# 8bit_RAM.net
KiCad netlist of a schematic drawn in Altium Designer
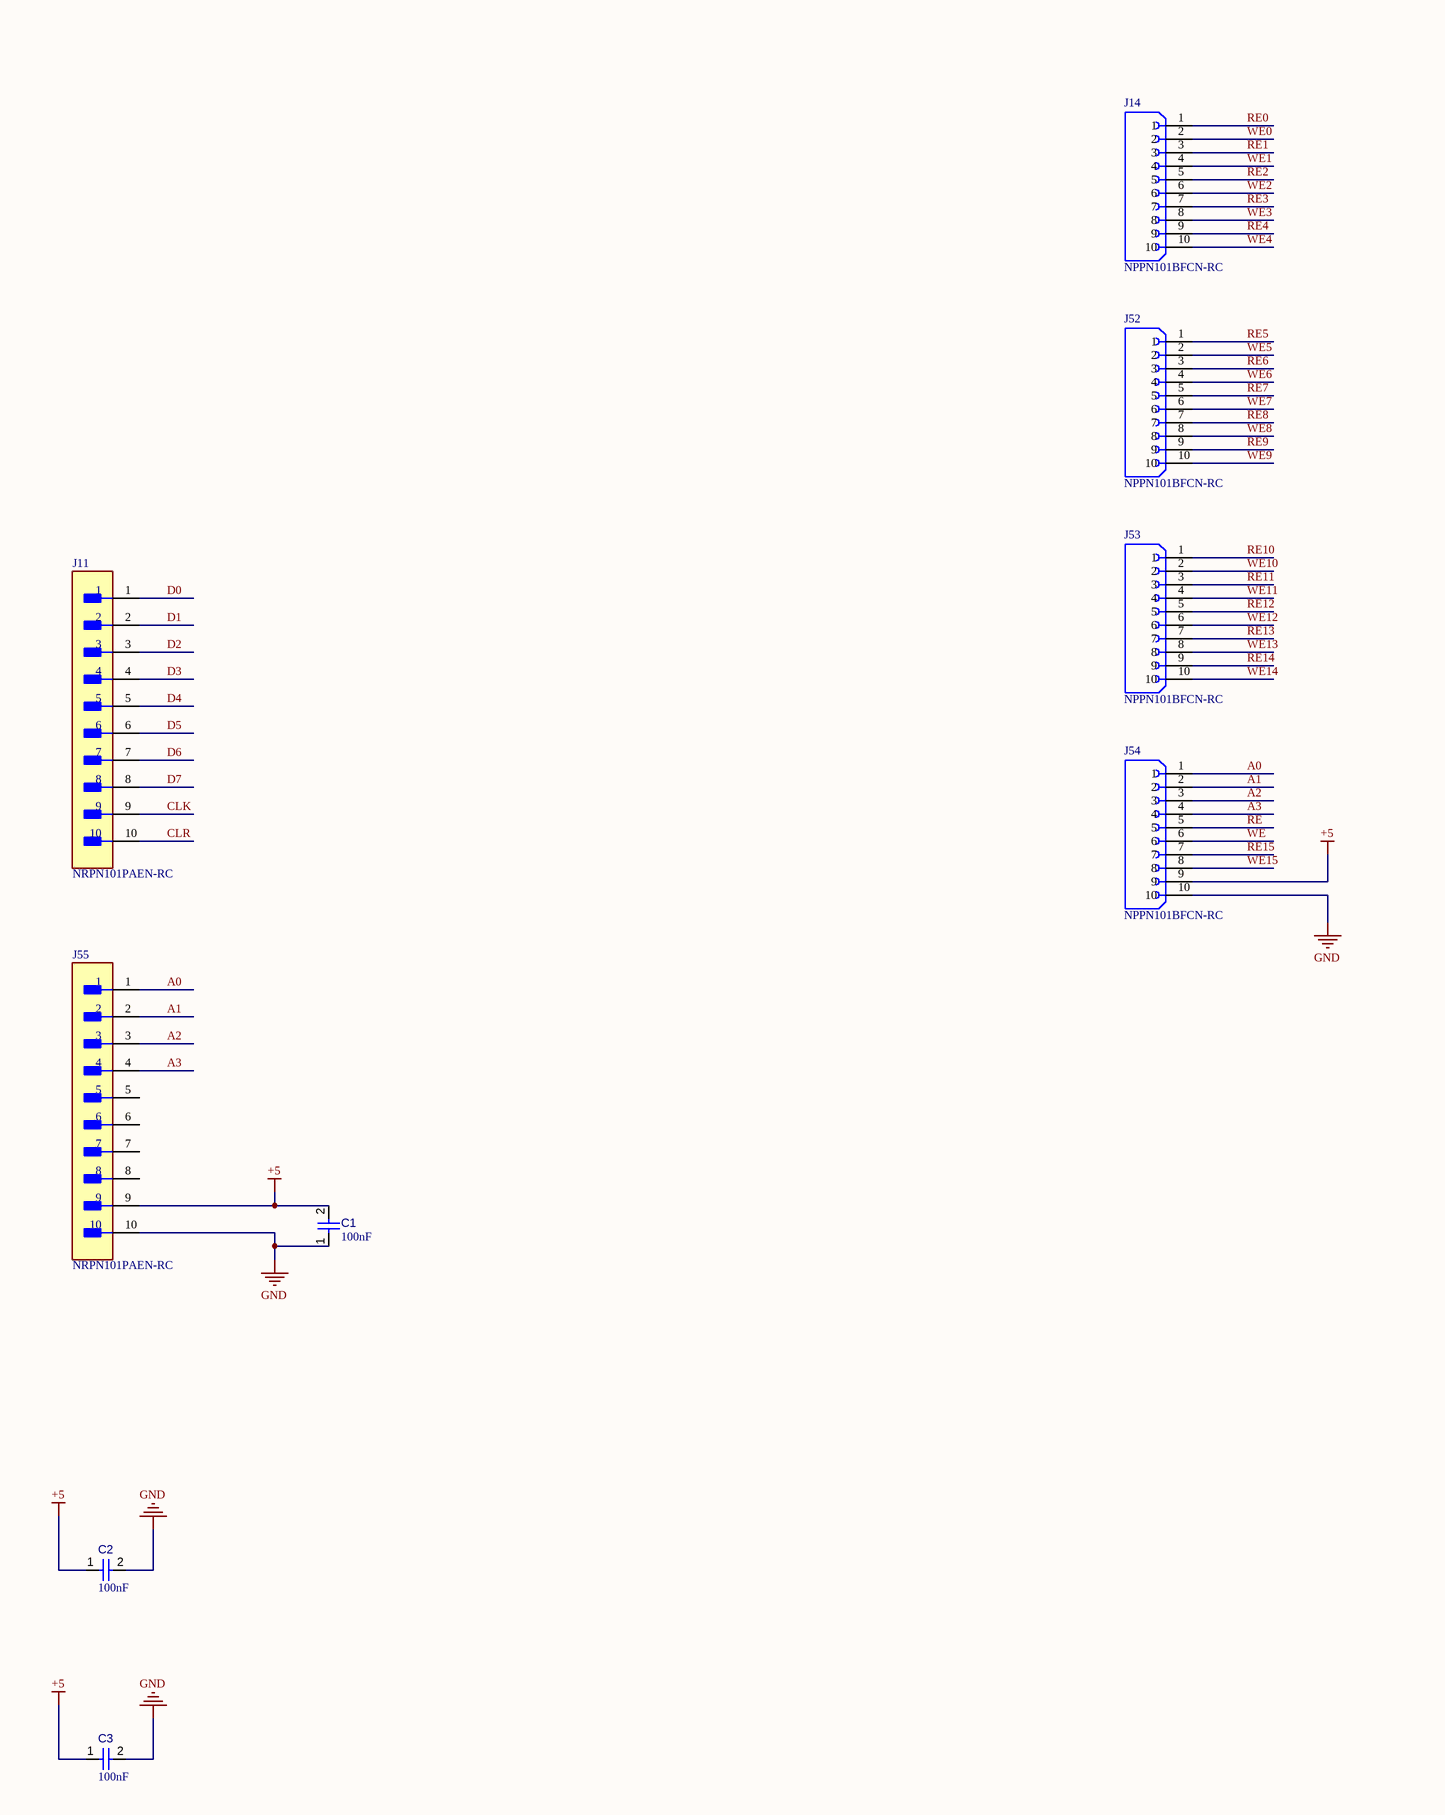
[diagram p0: 8bit_RAM.SchDoc, top left]
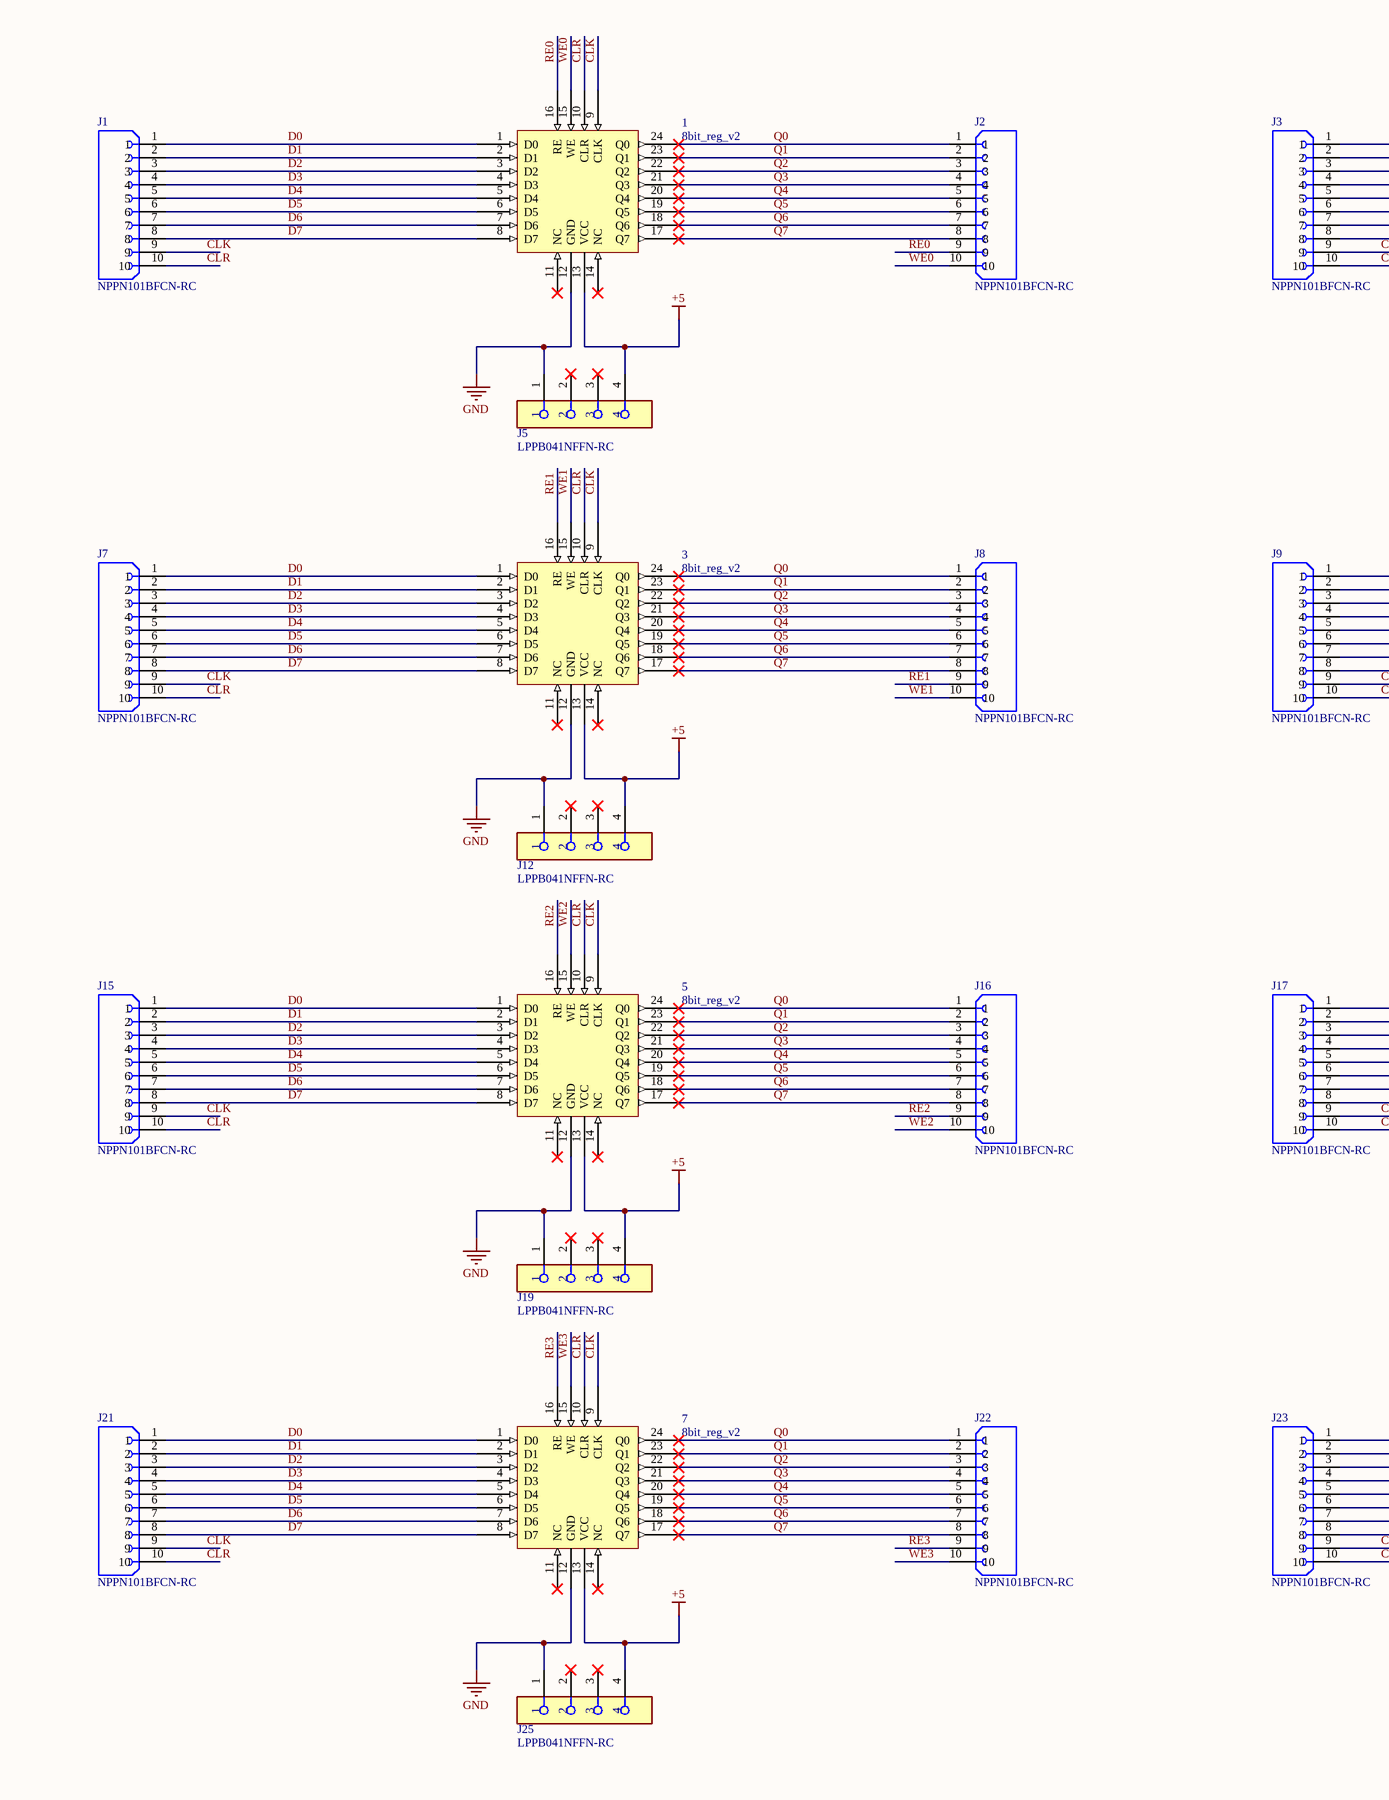
[diagram p1: 8bit_RAM.SchDoc, top middle]
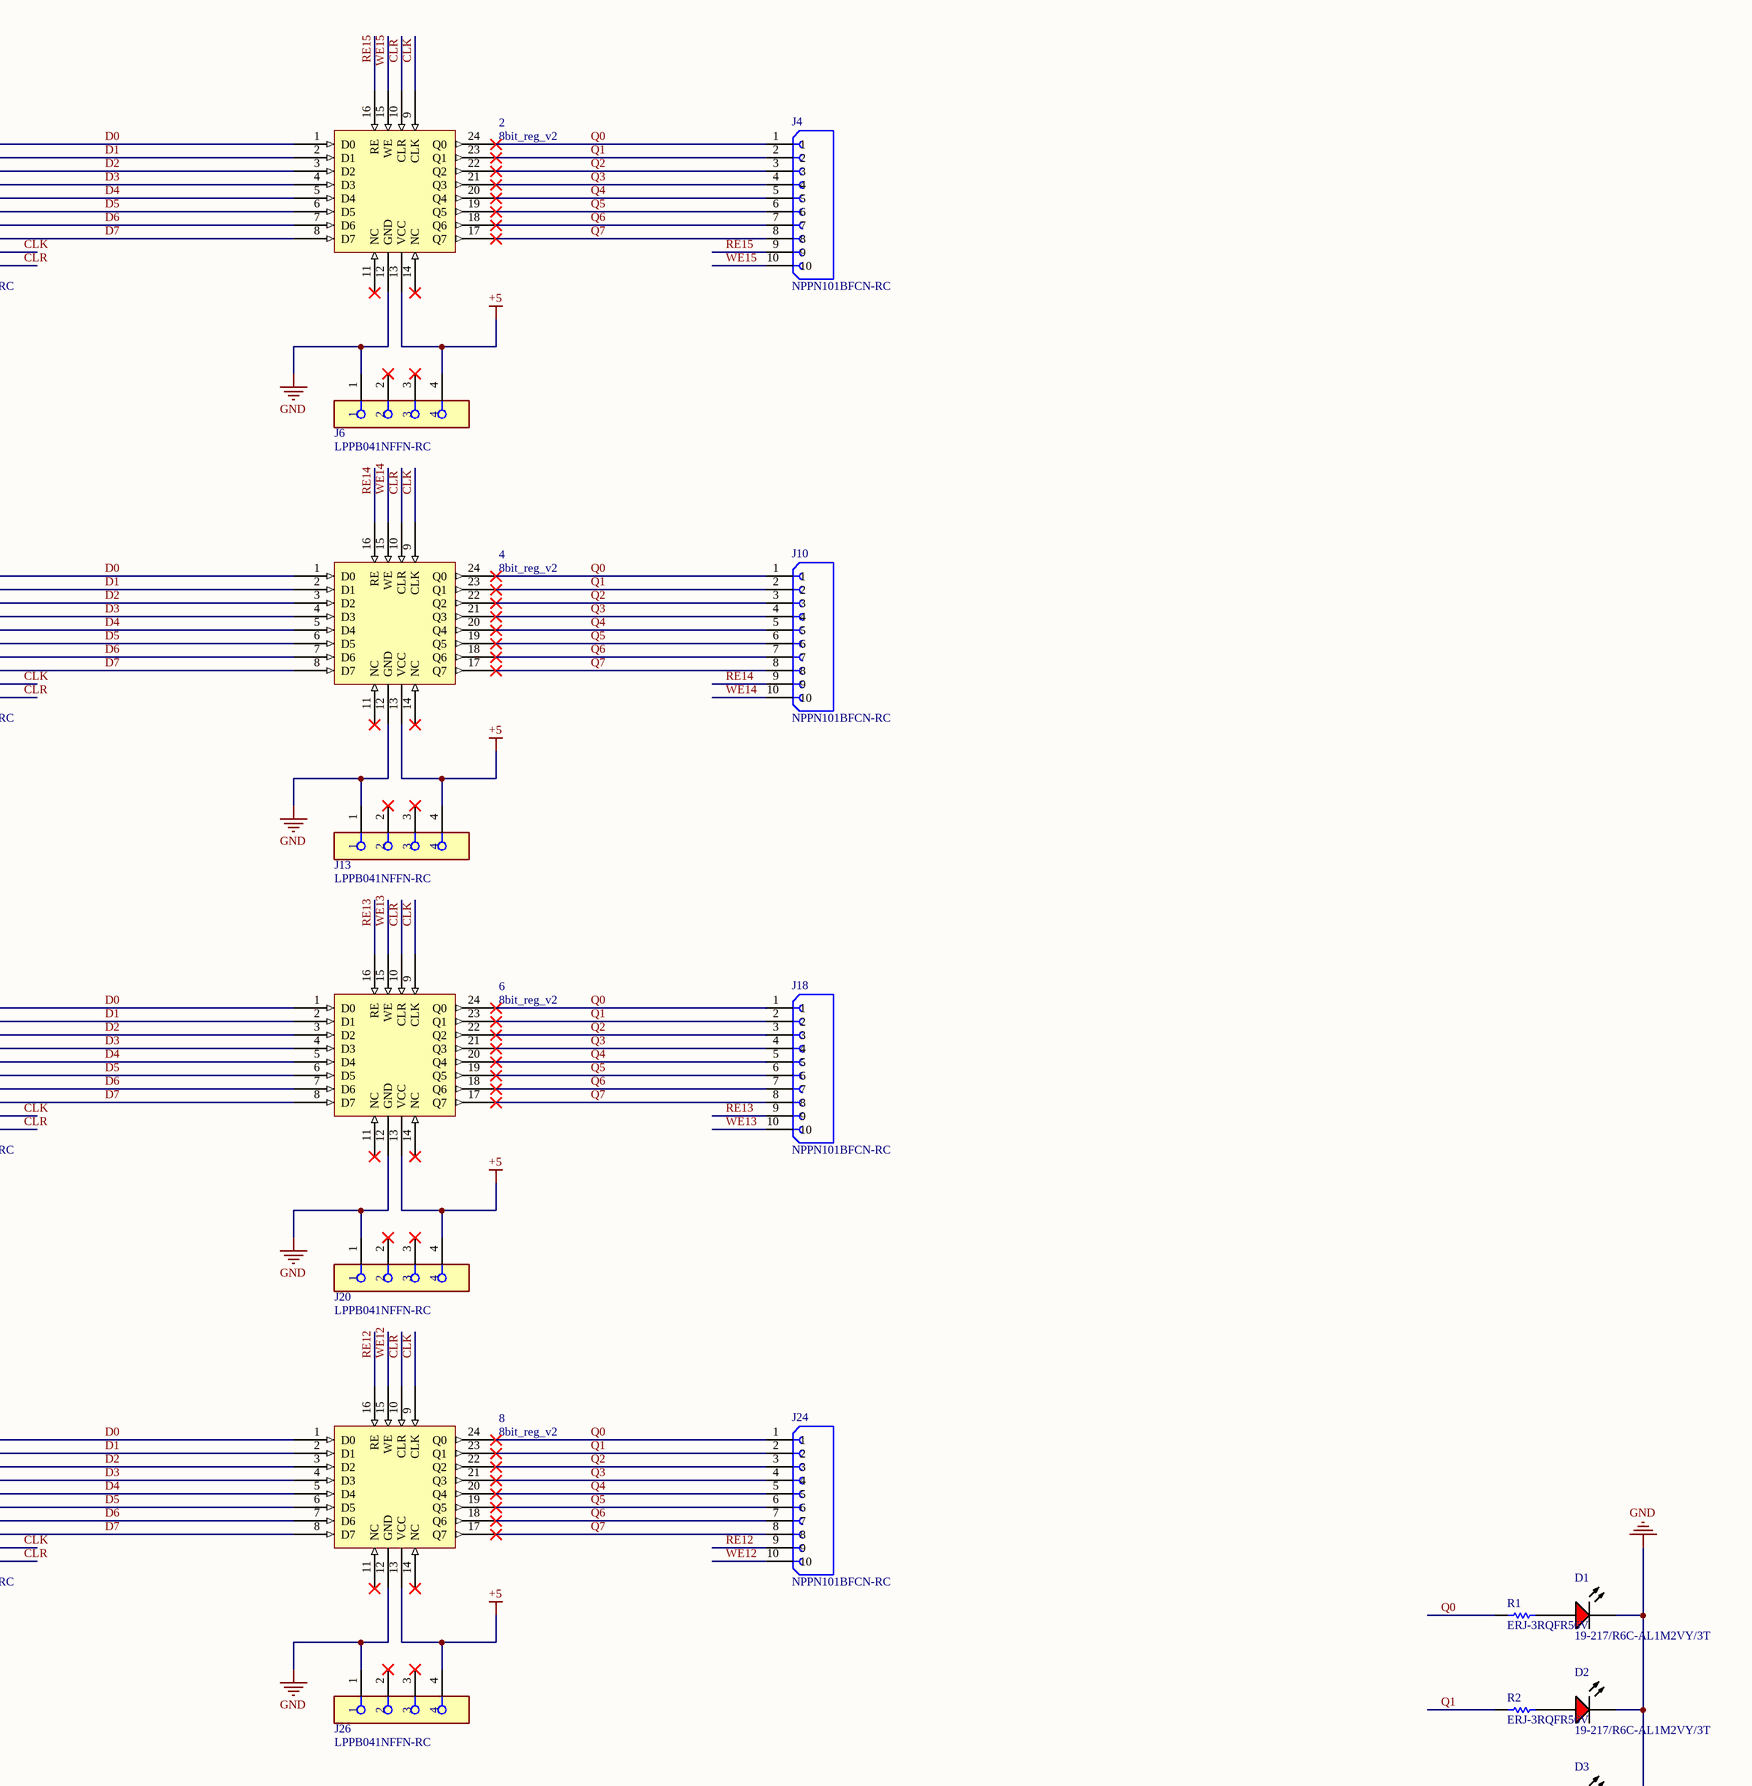
[diagram p2: 8bit_RAM.SchDoc, top right]
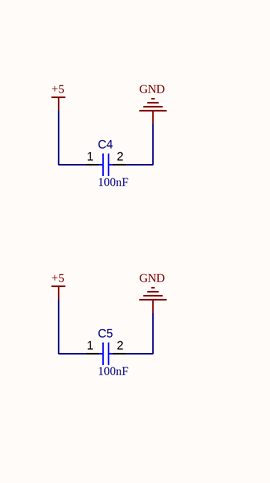
[diagram p3: 8bit_RAM.SchDoc, bottom left]
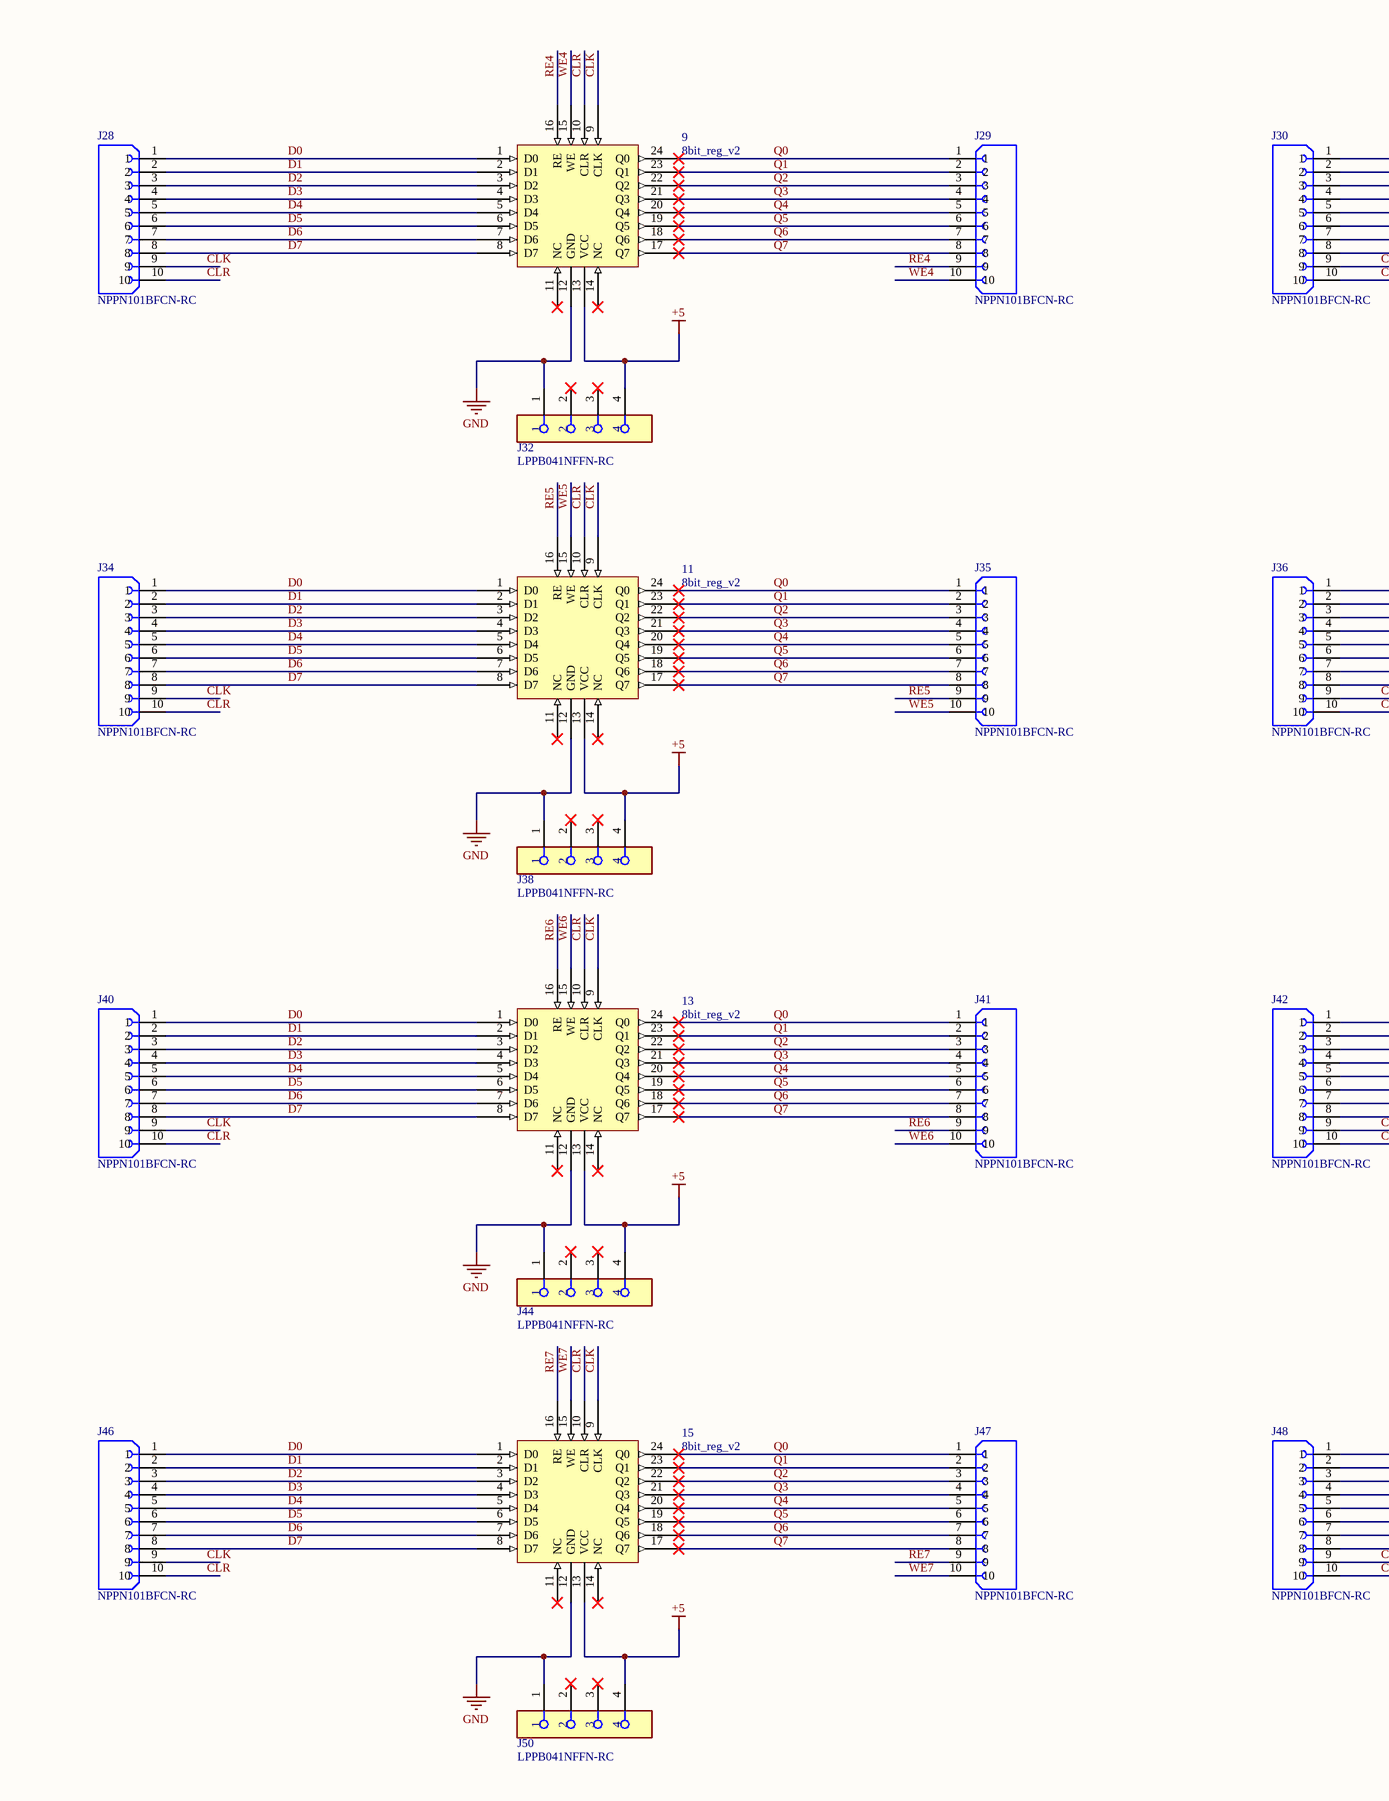
[diagram p4: 8bit_RAM.SchDoc, bottom middle]
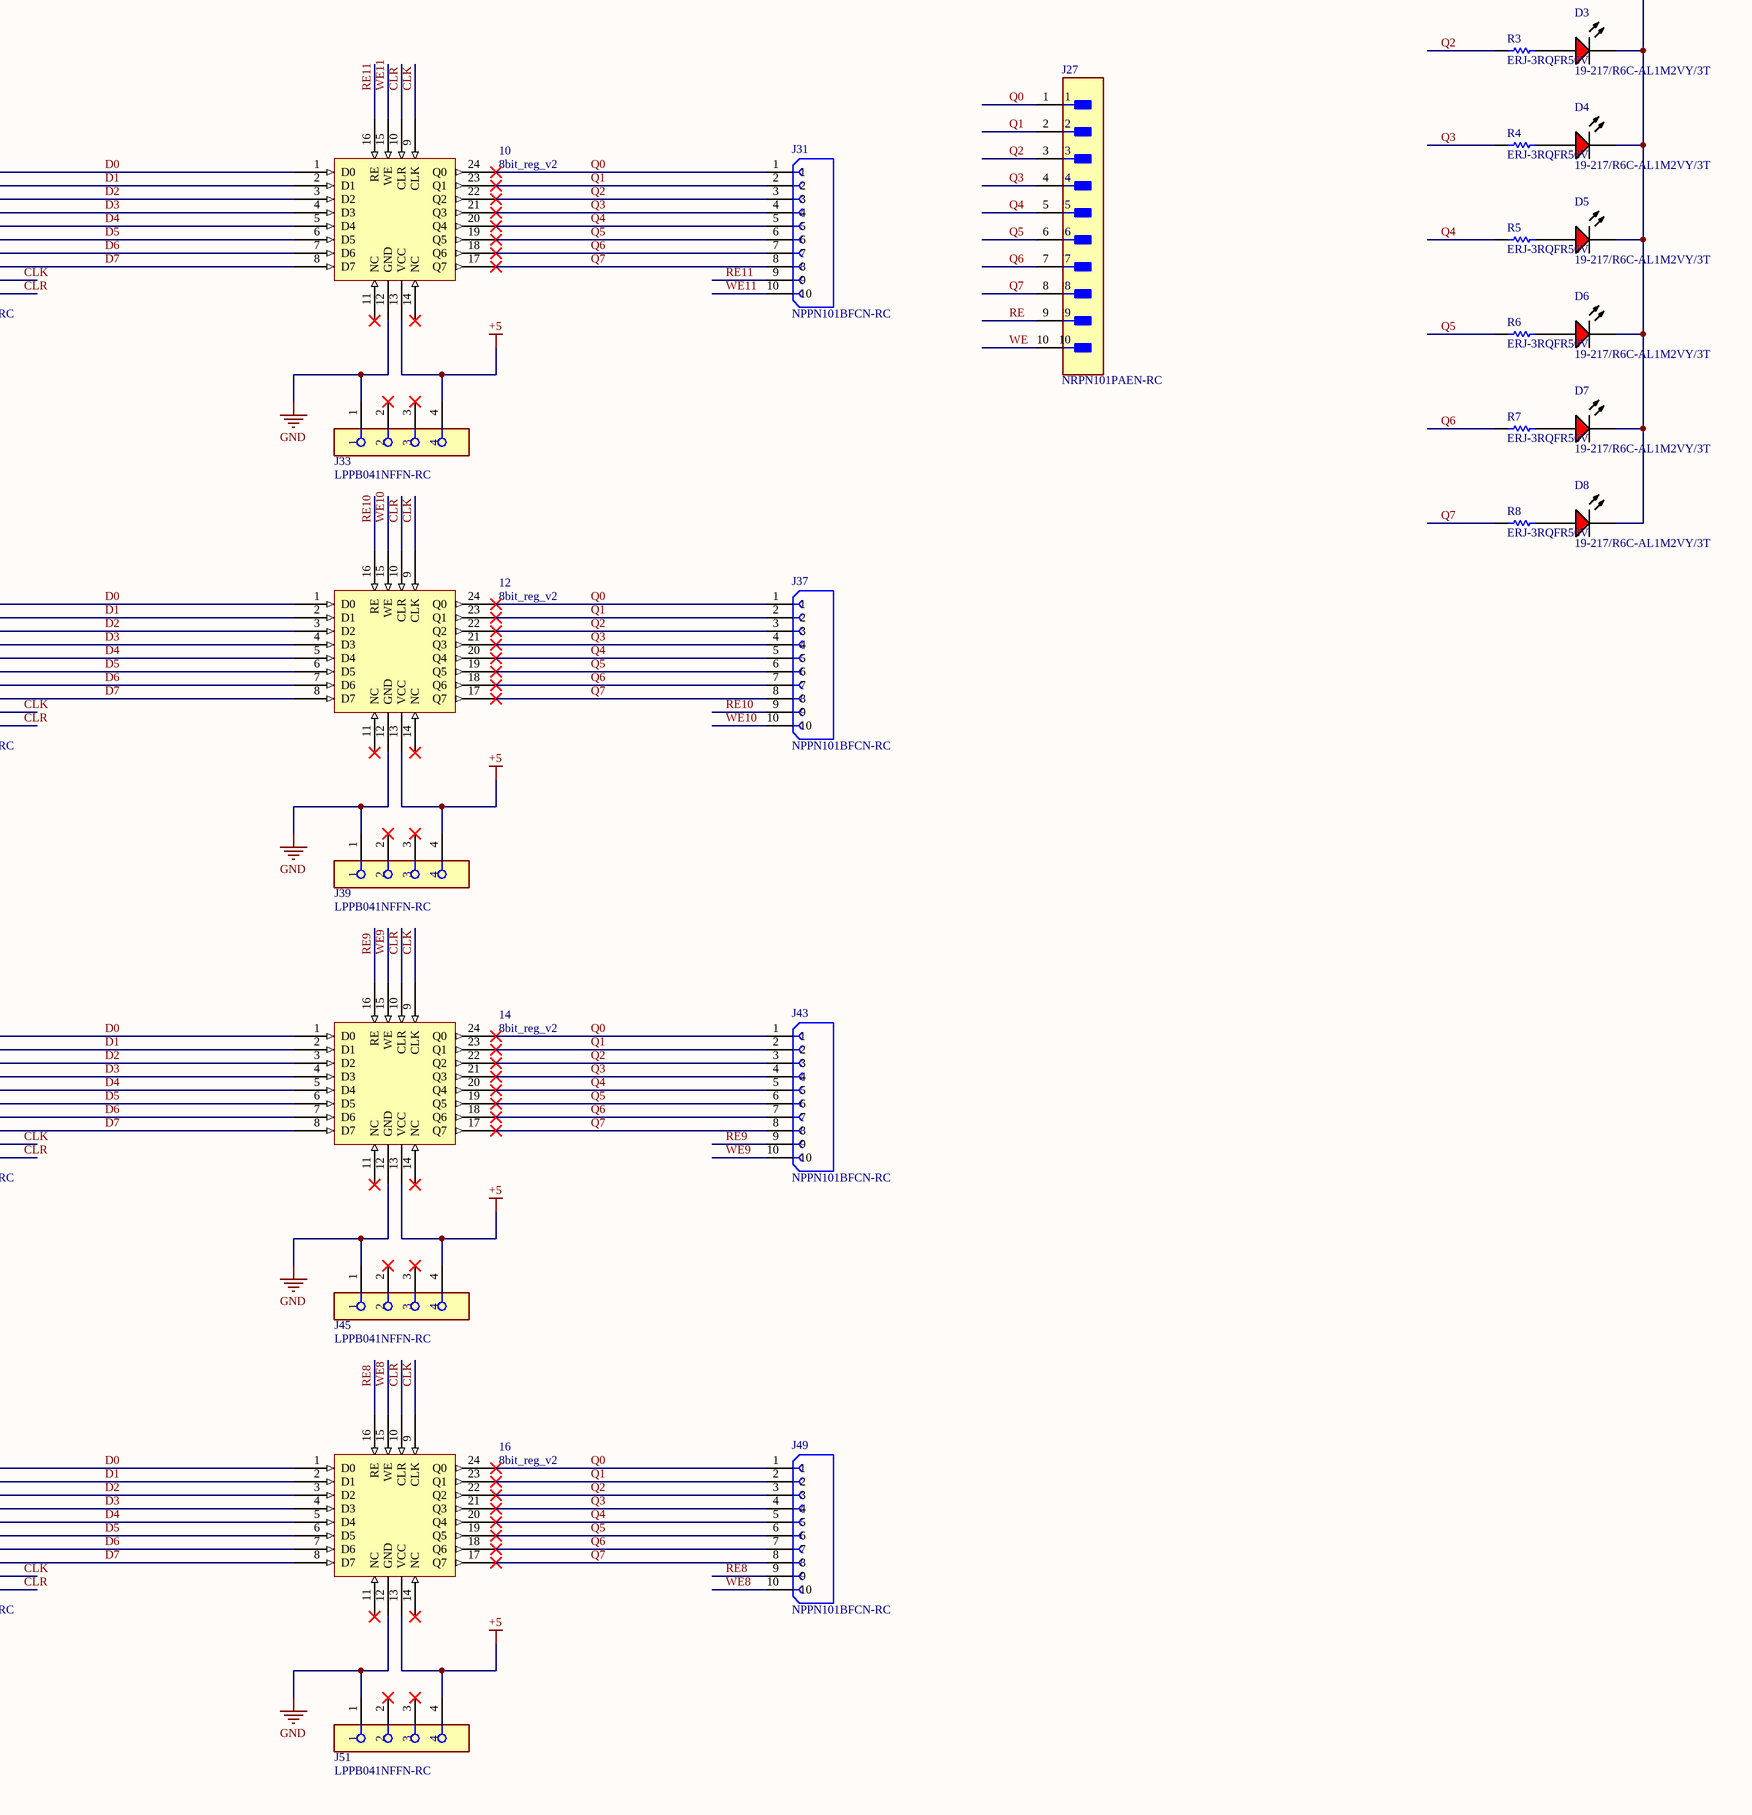
[diagram p5: 8bit_RAM.SchDoc, bottom right]

(export (version "E")
  (design (tool "Eeschema 10.0.6"))
  (components
    (comp (ref "1") (value "8bit_reg_v2") (libsource (lib "GOZ - Altium 365 cloud") (part "Custom Register")))
    (comp (ref "2") (value "8bit_reg_v2") (libsource (lib "GOZ - Altium 365 cloud") (part "Custom Register")))
    (comp (ref "3") (value "8bit_reg_v2") (libsource (lib "GOZ - Altium 365 cloud") (part "Custom Register")))
    (comp (ref "4") (value "8bit_reg_v2") (libsource (lib "GOZ - Altium 365 cloud") (part "Custom Register")))
    (comp (ref "5") (value "8bit_reg_v2") (libsource (lib "GOZ - Altium 365 cloud") (part "Custom Register")))
    (comp (ref "6") (value "8bit_reg_v2") (libsource (lib "GOZ - Altium 365 cloud") (part "Custom Register")))
    (comp (ref "7") (value "8bit_reg_v2") (libsource (lib "GOZ - Altium 365 cloud") (part "Custom Register")))
    (comp (ref "8") (value "8bit_reg_v2") (libsource (lib "GOZ - Altium 365 cloud") (part "Custom Register")))
    (comp (ref "9") (value "8bit_reg_v2") (libsource (lib "GOZ - Altium 365 cloud") (part "Custom Register")))
    (comp (ref "10")
      (value "8bit_reg_v2")
      (libsource (lib "GOZ - Altium 365 cloud") (part "Custom Register"))
    )
    (comp (ref "11")
      (value "8bit_reg_v2")
      (libsource (lib "GOZ - Altium 365 cloud") (part "Custom Register"))
    )
    (comp (ref "12")
      (value "8bit_reg_v2")
      (libsource (lib "GOZ - Altium 365 cloud") (part "Custom Register"))
    )
    (comp (ref "13")
      (value "8bit_reg_v2")
      (libsource (lib "GOZ - Altium 365 cloud") (part "Custom Register"))
    )
    (comp (ref "14")
      (value "8bit_reg_v2")
      (libsource (lib "GOZ - Altium 365 cloud") (part "Custom Register"))
    )
    (comp (ref "15")
      (value "8bit_reg_v2")
      (libsource (lib "GOZ - Altium 365 cloud") (part "Custom Register"))
    )
    (comp (ref "16")
      (value "8bit_reg_v2")
      (libsource (lib "GOZ - Altium 365 cloud") (part "Custom Register"))
    )
    (comp (ref "C1")
      (value "100nF")
      (footprint "CAPC1608X90X40NL10T20")
      (description "Chip Capacitor, 100 nF, +/- 10%, 50 V, 0603 (1608 Metric)")
      (fields (field (name "TOLERANCE") "10%") (field (name "Comment") "Capacitor 100 nF +/-10% 50 V 0603"))
      (libsource (lib "GOZ - Altium 365 cloud") (part "CAP-NP-2"))
    )
    (comp (ref "C2")
      (value "100nF")
      (footprint "CAPC1608X90X40NL10T20")
      (description "Chip Capacitor, 100 nF, +/- 10%, 50 V, 0603 (1608 Metric)")
      (fields (field (name "TOLERANCE") "10%") (field (name "Comment") "Capacitor 100 nF +/-10% 50 V 0603"))
      (libsource (lib "GOZ - Altium 365 cloud") (part "CAP-NP-2"))
    )
    (comp (ref "C3")
      (value "100nF")
      (footprint "CAPC1608X90X40NL10T20")
      (description "Chip Capacitor, 100 nF, +/- 10%, 50 V, 0603 (1608 Metric)")
      (fields (field (name "TOLERANCE") "10%") (field (name "Comment") "Capacitor 100 nF +/-10% 50 V 0603"))
      (libsource (lib "GOZ - Altium 365 cloud") (part "CAP-NP-2"))
    )
    (comp (ref "C4")
      (value "100nF")
      (footprint "CAPC1608X90X40NL10T20")
      (description "Chip Capacitor, 100 nF, +/- 10%, 50 V, 0603 (1608 Metric)")
      (fields (field (name "TOLERANCE") "10%") (field (name "Comment") "Capacitor 100 nF +/-10% 50 V 0603"))
      (libsource (lib "GOZ - Altium 365 cloud") (part "CAP-NP-2"))
    )
    (comp (ref "C5")
      (value "100nF")
      (footprint "CAPC1608X90X40NL10T20")
      (description "Chip Capacitor, 100 nF, +/- 10%, 50 V, 0603 (1608 Metric)")
      (fields (field (name "TOLERANCE") "10%") (field (name "Comment") "Capacitor 100 nF +/-10% 50 V 0603"))
      (libsource (lib "GOZ - Altium 365 cloud") (part "CAP-NP-2"))
    )
    (comp (ref "D1")
      (value "19-217/R6C-AL1M2VY/3T")
      (footprint "EVRL-0603-2_V")
      (description "Chip LED, Red, 5 V, 25 mA, -40 to 85 degC, 2-Pin SMD (0603), RoHS, Tape and Reel")
      (fields (field (name "MANUFACTURER") "Everlight Electronics"))
      (libsource (lib "GOZ - Altium 365 cloud") (part "LED-RED-AK-2"))
    )
    (comp (ref "D2")
      (value "19-217/R6C-AL1M2VY/3T")
      (footprint "EVRL-0603-2_V")
      (description "Chip LED, Red, 5 V, 25 mA, -40 to 85 degC, 2-Pin SMD (0603), RoHS, Tape and Reel")
      (fields (field (name "MANUFACTURER") "Everlight Electronics"))
      (libsource (lib "GOZ - Altium 365 cloud") (part "LED-RED-AK-2"))
    )
    (comp (ref "D3")
      (value "19-217/R6C-AL1M2VY/3T")
      (footprint "EVRL-0603-2_V")
      (description "Chip LED, Red, 5 V, 25 mA, -40 to 85 degC, 2-Pin SMD (0603), RoHS, Tape and Reel")
      (fields (field (name "MANUFACTURER") "Everlight Electronics"))
      (libsource (lib "GOZ - Altium 365 cloud") (part "LED-RED-AK-2"))
    )
    (comp (ref "D4")
      (value "19-217/R6C-AL1M2VY/3T")
      (footprint "EVRL-0603-2_V")
      (description "Chip LED, Red, 5 V, 25 mA, -40 to 85 degC, 2-Pin SMD (0603), RoHS, Tape and Reel")
      (fields (field (name "MANUFACTURER") "Everlight Electronics"))
      (libsource (lib "GOZ - Altium 365 cloud") (part "LED-RED-AK-2"))
    )
    (comp (ref "D5")
      (value "19-217/R6C-AL1M2VY/3T")
      (footprint "EVRL-0603-2_V")
      (description "Chip LED, Red, 5 V, 25 mA, -40 to 85 degC, 2-Pin SMD (0603), RoHS, Tape and Reel")
      (fields (field (name "MANUFACTURER") "Everlight Electronics"))
      (libsource (lib "GOZ - Altium 365 cloud") (part "LED-RED-AK-2"))
    )
    (comp (ref "D6")
      (value "19-217/R6C-AL1M2VY/3T")
      (footprint "EVRL-0603-2_V")
      (description "Chip LED, Red, 5 V, 25 mA, -40 to 85 degC, 2-Pin SMD (0603), RoHS, Tape and Reel")
      (fields (field (name "MANUFACTURER") "Everlight Electronics"))
      (libsource (lib "GOZ - Altium 365 cloud") (part "LED-RED-AK-2"))
    )
    (comp (ref "D7")
      (value "19-217/R6C-AL1M2VY/3T")
      (footprint "EVRL-0603-2_V")
      (description "Chip LED, Red, 5 V, 25 mA, -40 to 85 degC, 2-Pin SMD (0603), RoHS, Tape and Reel")
      (fields (field (name "MANUFACTURER") "Everlight Electronics"))
      (libsource (lib "GOZ - Altium 365 cloud") (part "LED-RED-AK-2"))
    )
    (comp (ref "D8")
      (value "19-217/R6C-AL1M2VY/3T")
      (footprint "EVRL-0603-2_V")
      (description "Chip LED, Red, 5 V, 25 mA, -40 to 85 degC, 2-Pin SMD (0603), RoHS, Tape and Reel")
      (fields (field (name "MANUFACTURER") "Everlight Electronics"))
      (libsource (lib "GOZ - Altium 365 cloud") (part "LED-RED-AK-2"))
    )
    (comp (ref "J1")
      (value "NPPN101BFCN-RC")
      (footprint "SULLINS_NPPN101BFCN-RC")
      (description "10 Position Header Connector 0.079 (2.00mm) Through Hole Gold")
      (fields (field (name "MF") "Sullins Connector"))
      (libsource (lib "") (part "NPPN101BFCN-RC_1"))
    )
    (comp (ref "J2")
      (value "NPPN101BFCN-RC")
      (footprint "SULLINS_NPPN101BFCN-RC")
      (description "10 Position Header Connector 0.079 (2.00mm) Through Hole Gold")
      (fields (field (name "MF") "Sullins Connector"))
      (libsource (lib "GOZ - Altium 365 cloud") (part "NPPN101BFCN-RC"))
    )
    (comp (ref "J3")
      (value "NPPN101BFCN-RC")
      (footprint "SULLINS_NPPN101BFCN-RC")
      (description "10 Position Header Connector 0.079 (2.00mm) Through Hole Gold")
      (fields (field (name "MF") "Sullins Connector"))
      (libsource (lib "") (part "NPPN101BFCN-RC_1"))
    )
    (comp (ref "J4")
      (value "NPPN101BFCN-RC")
      (footprint "SULLINS_NPPN101BFCN-RC")
      (description "10 Position Header Connector 0.079 (2.00mm) Through Hole Gold")
      (fields (field (name "MF") "Sullins Connector"))
      (libsource (lib "GOZ - Altium 365 cloud") (part "NPPN101BFCN-RC"))
    )
    (comp (ref "J5")
      (value "LPPB041NFFN-RC")
      (footprint "FP-LPPB041NFFN-RC-MFG")
      (description "CONN HDR 4POS 0.05 GOLD PCB")
      (libsource (lib "Altium Content Vault") (part "56792406a6bd5c25e158f553ecd1aa7"))
    )
    (comp (ref "J6")
      (value "LPPB041NFFN-RC")
      (footprint "FP-LPPB041NFFN-RC-MFG")
      (description "CONN HDR 4POS 0.05 GOLD PCB")
      (libsource (lib "Altium Content Vault") (part "56792406a6bd5c25e158f553ecd1aa7"))
    )
    (comp (ref "J7")
      (value "NPPN101BFCN-RC")
      (footprint "SULLINS_NPPN101BFCN-RC")
      (description "10 Position Header Connector 0.079 (2.00mm) Through Hole Gold")
      (fields (field (name "MF") "Sullins Connector"))
      (libsource (lib "") (part "NPPN101BFCN-RC_1"))
    )
    (comp (ref "J8")
      (value "NPPN101BFCN-RC")
      (footprint "SULLINS_NPPN101BFCN-RC")
      (description "10 Position Header Connector 0.079 (2.00mm) Through Hole Gold")
      (fields (field (name "MF") "Sullins Connector"))
      (libsource (lib "GOZ - Altium 365 cloud") (part "NPPN101BFCN-RC"))
    )
    (comp (ref "J9")
      (value "NPPN101BFCN-RC")
      (footprint "SULLINS_NPPN101BFCN-RC")
      (description "10 Position Header Connector 0.079 (2.00mm) Through Hole Gold")
      (fields (field (name "MF") "Sullins Connector"))
      (libsource (lib "") (part "NPPN101BFCN-RC_1"))
    )
    (comp (ref "J10")
      (value "NPPN101BFCN-RC")
      (footprint "SULLINS_NPPN101BFCN-RC")
      (description "10 Position Header Connector 0.079 (2.00mm) Through Hole Gold")
      (fields (field (name "MF") "Sullins Connector"))
      (libsource (lib "GOZ - Altium 365 cloud") (part "NPPN101BFCN-RC"))
    )
    (comp (ref "J11")
      (value "NRPN101PAEN-RC")
      (footprint "FP-NRPN101PAEN-RC-MFG")
      (description "CONN HEADER VERT 10POS 2MM")
      (fields
        (field (name "OCTOPART") "https://octopart.com/nrpn101paen-rc-sullins-18674398")
        (field (name "MANUFACTURER") "Sullins")
      )
      (libsource (lib "") (part "aee40dc8b284c03a16094555aa210be_1"))
    )
    (comp (ref "J12")
      (value "LPPB041NFFN-RC")
      (footprint "FP-LPPB041NFFN-RC-MFG")
      (description "CONN HDR 4POS 0.05 GOLD PCB")
      (libsource (lib "Altium Content Vault") (part "56792406a6bd5c25e158f553ecd1aa7"))
    )
    (comp (ref "J13")
      (value "LPPB041NFFN-RC")
      (footprint "FP-LPPB041NFFN-RC-MFG")
      (description "CONN HDR 4POS 0.05 GOLD PCB")
      (libsource (lib "Altium Content Vault") (part "56792406a6bd5c25e158f553ecd1aa7"))
    )
    (comp (ref "J14")
      (value "NPPN101BFCN-RC")
      (footprint "SULLINS_NPPN101BFCN-RC")
      (description "10 Position Header Connector 0.079 (2.00mm) Through Hole Gold")
      (fields (field (name "MF") "Sullins Connector"))
      (libsource (lib "") (part "NPPN101BFCN-RC_1"))
    )
    (comp (ref "J15")
      (value "NPPN101BFCN-RC")
      (footprint "SULLINS_NPPN101BFCN-RC")
      (description "10 Position Header Connector 0.079 (2.00mm) Through Hole Gold")
      (fields (field (name "MF") "Sullins Connector"))
      (libsource (lib "") (part "NPPN101BFCN-RC_1"))
    )
    (comp (ref "J16")
      (value "NPPN101BFCN-RC")
      (footprint "SULLINS_NPPN101BFCN-RC")
      (description "10 Position Header Connector 0.079 (2.00mm) Through Hole Gold")
      (fields (field (name "MF") "Sullins Connector"))
      (libsource (lib "GOZ - Altium 365 cloud") (part "NPPN101BFCN-RC"))
    )
    (comp (ref "J17")
      (value "NPPN101BFCN-RC")
      (footprint "SULLINS_NPPN101BFCN-RC")
      (description "10 Position Header Connector 0.079 (2.00mm) Through Hole Gold")
      (fields (field (name "MF") "Sullins Connector"))
      (libsource (lib "") (part "NPPN101BFCN-RC_1"))
    )
    (comp (ref "J18")
      (value "NPPN101BFCN-RC")
      (footprint "SULLINS_NPPN101BFCN-RC")
      (description "10 Position Header Connector 0.079 (2.00mm) Through Hole Gold")
      (fields (field (name "MF") "Sullins Connector"))
      (libsource (lib "GOZ - Altium 365 cloud") (part "NPPN101BFCN-RC"))
    )
    (comp (ref "J19")
      (value "LPPB041NFFN-RC")
      (footprint "FP-LPPB041NFFN-RC-MFG")
      (description "CONN HDR 4POS 0.05 GOLD PCB")
      (libsource (lib "Altium Content Vault") (part "56792406a6bd5c25e158f553ecd1aa7"))
    )
    (comp (ref "J20")
      (value "LPPB041NFFN-RC")
      (footprint "FP-LPPB041NFFN-RC-MFG")
      (description "CONN HDR 4POS 0.05 GOLD PCB")
      (libsource (lib "Altium Content Vault") (part "56792406a6bd5c25e158f553ecd1aa7"))
    )
    (comp (ref "J21")
      (value "NPPN101BFCN-RC")
      (footprint "SULLINS_NPPN101BFCN-RC")
      (description "10 Position Header Connector 0.079 (2.00mm) Through Hole Gold")
      (fields (field (name "MF") "Sullins Connector"))
      (libsource (lib "") (part "NPPN101BFCN-RC_1"))
    )
    (comp (ref "J22")
      (value "NPPN101BFCN-RC")
      (footprint "SULLINS_NPPN101BFCN-RC")
      (description "10 Position Header Connector 0.079 (2.00mm) Through Hole Gold")
      (fields (field (name "MF") "Sullins Connector"))
      (libsource (lib "GOZ - Altium 365 cloud") (part "NPPN101BFCN-RC"))
    )
    (comp (ref "J23")
      (value "NPPN101BFCN-RC")
      (footprint "SULLINS_NPPN101BFCN-RC")
      (description "10 Position Header Connector 0.079 (2.00mm) Through Hole Gold")
      (fields (field (name "MF") "Sullins Connector"))
      (libsource (lib "") (part "NPPN101BFCN-RC_1"))
    )
    (comp (ref "J24")
      (value "NPPN101BFCN-RC")
      (footprint "SULLINS_NPPN101BFCN-RC")
      (description "10 Position Header Connector 0.079 (2.00mm) Through Hole Gold")
      (fields (field (name "MF") "Sullins Connector"))
      (libsource (lib "GOZ - Altium 365 cloud") (part "NPPN101BFCN-RC"))
    )
    (comp (ref "J25")
      (value "LPPB041NFFN-RC")
      (footprint "FP-LPPB041NFFN-RC-MFG")
      (description "CONN HDR 4POS 0.05 GOLD PCB")
      (libsource (lib "Altium Content Vault") (part "56792406a6bd5c25e158f553ecd1aa7"))
    )
    (comp (ref "J26")
      (value "LPPB041NFFN-RC")
      (footprint "FP-LPPB041NFFN-RC-MFG")
      (description "CONN HDR 4POS 0.05 GOLD PCB")
      (libsource (lib "Altium Content Vault") (part "56792406a6bd5c25e158f553ecd1aa7"))
    )
    (comp (ref "J27")
      (value "NRPN101PAEN-RC")
      (footprint "FP-NRPN101PAEN-RC-MFG")
      (description "CONN HEADER VERT 10POS 2MM")
      (fields
        (field (name "OCTOPART") "https://octopart.com/nrpn101paen-rc-sullins-18674398")
        (field (name "MANUFACTURER") "Sullins")
      )
      (libsource (lib "Altium Content Vault") (part "aee40dc8b284c03a16094555aa210be"))
    )
    (comp (ref "J28")
      (value "NPPN101BFCN-RC")
      (footprint "SULLINS_NPPN101BFCN-RC")
      (description "10 Position Header Connector 0.079 (2.00mm) Through Hole Gold")
      (fields (field (name "MF") "Sullins Connector"))
      (libsource (lib "") (part "NPPN101BFCN-RC_1"))
    )
    (comp (ref "J29")
      (value "NPPN101BFCN-RC")
      (footprint "SULLINS_NPPN101BFCN-RC")
      (description "10 Position Header Connector 0.079 (2.00mm) Through Hole Gold")
      (fields (field (name "MF") "Sullins Connector"))
      (libsource (lib "GOZ - Altium 365 cloud") (part "NPPN101BFCN-RC"))
    )
    (comp (ref "J30")
      (value "NPPN101BFCN-RC")
      (footprint "SULLINS_NPPN101BFCN-RC")
      (description "10 Position Header Connector 0.079 (2.00mm) Through Hole Gold")
      (fields (field (name "MF") "Sullins Connector"))
      (libsource (lib "") (part "NPPN101BFCN-RC_1"))
    )
    (comp (ref "J31")
      (value "NPPN101BFCN-RC")
      (footprint "SULLINS_NPPN101BFCN-RC")
      (description "10 Position Header Connector 0.079 (2.00mm) Through Hole Gold")
      (fields (field (name "MF") "Sullins Connector"))
      (libsource (lib "GOZ - Altium 365 cloud") (part "NPPN101BFCN-RC"))
    )
    (comp (ref "J32")
      (value "LPPB041NFFN-RC")
      (footprint "FP-LPPB041NFFN-RC-MFG")
      (description "CONN HDR 4POS 0.05 GOLD PCB")
      (libsource (lib "Altium Content Vault") (part "56792406a6bd5c25e158f553ecd1aa7"))
    )
    (comp (ref "J33")
      (value "LPPB041NFFN-RC")
      (footprint "FP-LPPB041NFFN-RC-MFG")
      (description "CONN HDR 4POS 0.05 GOLD PCB")
      (libsource (lib "Altium Content Vault") (part "56792406a6bd5c25e158f553ecd1aa7"))
    )
    (comp (ref "J34")
      (value "NPPN101BFCN-RC")
      (footprint "SULLINS_NPPN101BFCN-RC")
      (description "10 Position Header Connector 0.079 (2.00mm) Through Hole Gold")
      (fields (field (name "MF") "Sullins Connector"))
      (libsource (lib "") (part "NPPN101BFCN-RC_1"))
    )
    (comp (ref "J35")
      (value "NPPN101BFCN-RC")
      (footprint "SULLINS_NPPN101BFCN-RC")
      (description "10 Position Header Connector 0.079 (2.00mm) Through Hole Gold")
      (fields (field (name "MF") "Sullins Connector"))
      (libsource (lib "GOZ - Altium 365 cloud") (part "NPPN101BFCN-RC"))
    )
    (comp (ref "J36")
      (value "NPPN101BFCN-RC")
      (footprint "SULLINS_NPPN101BFCN-RC")
      (description "10 Position Header Connector 0.079 (2.00mm) Through Hole Gold")
      (fields (field (name "MF") "Sullins Connector"))
      (libsource (lib "") (part "NPPN101BFCN-RC_1"))
    )
    (comp (ref "J37")
      (value "NPPN101BFCN-RC")
      (footprint "SULLINS_NPPN101BFCN-RC")
      (description "10 Position Header Connector 0.079 (2.00mm) Through Hole Gold")
      (fields (field (name "MF") "Sullins Connector"))
      (libsource (lib "GOZ - Altium 365 cloud") (part "NPPN101BFCN-RC"))
    )
    (comp (ref "J38")
      (value "LPPB041NFFN-RC")
      (footprint "FP-LPPB041NFFN-RC-MFG")
      (description "CONN HDR 4POS 0.05 GOLD PCB")
      (libsource (lib "Altium Content Vault") (part "56792406a6bd5c25e158f553ecd1aa7"))
    )
    (comp (ref "J39")
      (value "LPPB041NFFN-RC")
      (footprint "FP-LPPB041NFFN-RC-MFG")
      (description "CONN HDR 4POS 0.05 GOLD PCB")
      (libsource (lib "Altium Content Vault") (part "56792406a6bd5c25e158f553ecd1aa7"))
    )
    (comp (ref "J40")
      (value "NPPN101BFCN-RC")
      (footprint "SULLINS_NPPN101BFCN-RC")
      (description "10 Position Header Connector 0.079 (2.00mm) Through Hole Gold")
      (fields (field (name "MF") "Sullins Connector"))
      (libsource (lib "") (part "NPPN101BFCN-RC_1"))
    )
    (comp (ref "J41")
      (value "NPPN101BFCN-RC")
      (footprint "SULLINS_NPPN101BFCN-RC")
      (description "10 Position Header Connector 0.079 (2.00mm) Through Hole Gold")
      (fields (field (name "MF") "Sullins Connector"))
      (libsource (lib "GOZ - Altium 365 cloud") (part "NPPN101BFCN-RC"))
    )
    (comp (ref "J42")
      (value "NPPN101BFCN-RC")
      (footprint "SULLINS_NPPN101BFCN-RC")
      (description "10 Position Header Connector 0.079 (2.00mm) Through Hole Gold")
      (fields (field (name "MF") "Sullins Connector"))
      (libsource (lib "") (part "NPPN101BFCN-RC_1"))
    )
    (comp (ref "J43")
      (value "NPPN101BFCN-RC")
      (footprint "SULLINS_NPPN101BFCN-RC")
      (description "10 Position Header Connector 0.079 (2.00mm) Through Hole Gold")
      (fields (field (name "MF") "Sullins Connector"))
      (libsource (lib "GOZ - Altium 365 cloud") (part "NPPN101BFCN-RC"))
    )
    (comp (ref "J44")
      (value "LPPB041NFFN-RC")
      (footprint "FP-LPPB041NFFN-RC-MFG")
      (description "CONN HDR 4POS 0.05 GOLD PCB")
      (libsource (lib "Altium Content Vault") (part "56792406a6bd5c25e158f553ecd1aa7"))
    )
    (comp (ref "J45")
      (value "LPPB041NFFN-RC")
      (footprint "FP-LPPB041NFFN-RC-MFG")
      (description "CONN HDR 4POS 0.05 GOLD PCB")
      (libsource (lib "Altium Content Vault") (part "56792406a6bd5c25e158f553ecd1aa7"))
    )
    (comp (ref "J46")
      (value "NPPN101BFCN-RC")
      (footprint "SULLINS_NPPN101BFCN-RC")
      (description "10 Position Header Connector 0.079 (2.00mm) Through Hole Gold")
      (fields (field (name "MF") "Sullins Connector"))
      (libsource (lib "") (part "NPPN101BFCN-RC_1"))
    )
    (comp (ref "J47")
      (value "NPPN101BFCN-RC")
      (footprint "SULLINS_NPPN101BFCN-RC")
      (description "10 Position Header Connector 0.079 (2.00mm) Through Hole Gold")
      (fields (field (name "MF") "Sullins Connector"))
      (libsource (lib "GOZ - Altium 365 cloud") (part "NPPN101BFCN-RC"))
    )
    (comp (ref "J48")
      (value "NPPN101BFCN-RC")
      (footprint "SULLINS_NPPN101BFCN-RC")
      (description "10 Position Header Connector 0.079 (2.00mm) Through Hole Gold")
      (fields (field (name "MF") "Sullins Connector"))
      (libsource (lib "") (part "NPPN101BFCN-RC_1"))
    )
    (comp (ref "J49")
      (value "NPPN101BFCN-RC")
      (footprint "SULLINS_NPPN101BFCN-RC")
      (description "10 Position Header Connector 0.079 (2.00mm) Through Hole Gold")
      (fields (field (name "MF") "Sullins Connector"))
      (libsource (lib "GOZ - Altium 365 cloud") (part "NPPN101BFCN-RC"))
    )
    (comp (ref "J50")
      (value "LPPB041NFFN-RC")
      (footprint "FP-LPPB041NFFN-RC-MFG")
      (description "CONN HDR 4POS 0.05 GOLD PCB")
      (libsource (lib "Altium Content Vault") (part "56792406a6bd5c25e158f553ecd1aa7"))
    )
    (comp (ref "J51")
      (value "LPPB041NFFN-RC")
      (footprint "FP-LPPB041NFFN-RC-MFG")
      (description "CONN HDR 4POS 0.05 GOLD PCB")
      (libsource (lib "Altium Content Vault") (part "56792406a6bd5c25e158f553ecd1aa7"))
    )
    (comp (ref "J52")
      (value "NPPN101BFCN-RC")
      (footprint "SULLINS_NPPN101BFCN-RC")
      (description "10 Position Header Connector 0.079 (2.00mm) Through Hole Gold")
      (fields (field (name "MF") "Sullins Connector"))
      (libsource (lib "") (part "NPPN101BFCN-RC_1"))
    )
    (comp (ref "J53")
      (value "NPPN101BFCN-RC")
      (footprint "SULLINS_NPPN101BFCN-RC")
      (description "10 Position Header Connector 0.079 (2.00mm) Through Hole Gold")
      (fields (field (name "MF") "Sullins Connector"))
      (libsource (lib "") (part "NPPN101BFCN-RC_1"))
    )
    (comp (ref "J54")
      (value "NPPN101BFCN-RC")
      (footprint "SULLINS_NPPN101BFCN-RC")
      (description "10 Position Header Connector 0.079 (2.00mm) Through Hole Gold")
      (fields (field (name "MF") "Sullins Connector"))
      (libsource (lib "") (part "NPPN101BFCN-RC_1"))
    )
    (comp (ref "J55")
      (value "NRPN101PAEN-RC")
      (footprint "FP-NRPN101PAEN-RC-MFG")
      (description "CONN HEADER VERT 10POS 2MM")
      (fields
        (field (name "OCTOPART") "https://octopart.com/nrpn101paen-rc-sullins-18674398")
        (field (name "MANUFACTURER") "Sullins")
      )
      (libsource (lib "") (part "aee40dc8b284c03a16094555aa210be_1"))
    )
    (comp (ref "R1")
      (value "ERJ-3RQFR56V")
      (footprint "RESC1608X55X30NL15T15")
      (fields (field (name "MANUFACTURER") "Panasonic"))
      (libsource (lib "Altium Content Vault") (part "RES"))
    )
    (comp (ref "R2")
      (value "ERJ-3RQFR56V")
      (footprint "RESC1608X55X30NL15T15")
      (fields (field (name "MANUFACTURER") "Panasonic"))
      (libsource (lib "Altium Content Vault") (part "RES"))
    )
    (comp (ref "R3")
      (value "ERJ-3RQFR56V")
      (footprint "RESC1608X55X30NL15T15")
      (fields (field (name "MANUFACTURER") "Panasonic"))
      (libsource (lib "Altium Content Vault") (part "RES"))
    )
    (comp (ref "R4")
      (value "ERJ-3RQFR56V")
      (footprint "RESC1608X55X30NL15T15")
      (fields (field (name "MANUFACTURER") "Panasonic"))
      (libsource (lib "Altium Content Vault") (part "RES"))
    )
    (comp (ref "R5")
      (value "ERJ-3RQFR56V")
      (footprint "RESC1608X55X30NL15T15")
      (fields (field (name "MANUFACTURER") "Panasonic"))
      (libsource (lib "Altium Content Vault") (part "RES"))
    )
    (comp (ref "R6")
      (value "ERJ-3RQFR56V")
      (footprint "RESC1608X55X30NL15T15")
      (fields (field (name "MANUFACTURER") "Panasonic"))
      (libsource (lib "Altium Content Vault") (part "RES"))
    )
    (comp (ref "R7")
      (value "ERJ-3RQFR56V")
      (footprint "RESC1608X55X30NL15T15")
      (fields (field (name "MANUFACTURER") "Panasonic"))
      (libsource (lib "Altium Content Vault") (part "RES"))
    )
    (comp (ref "R8")
      (value "ERJ-3RQFR56V")
      (footprint "RESC1608X55X30NL15T15")
      (fields (field (name "MANUFACTURER") "Panasonic"))
      (libsource (lib "Altium Content Vault") (part "RES"))
    )
  )
  (nets
    (net (code "1") (name "+5") (class "Default")
      (node (ref "1") (pin "13") (pinfunction "VCC_13") (pintype "power_in"))
      (node (ref "10") (pin "13") (pinfunction "VCC_13") (pintype "power_in"))
      (node (ref "11") (pin "13") (pinfunction "VCC_13") (pintype "power_in"))
      (node (ref "12") (pin "13") (pinfunction "VCC_13") (pintype "power_in"))
      (node (ref "13") (pin "13") (pinfunction "VCC_13") (pintype "power_in"))
      (node (ref "14") (pin "13") (pinfunction "VCC_13") (pintype "power_in"))
      (node (ref "15") (pin "13") (pinfunction "VCC_13") (pintype "power_in"))
      (node (ref "16") (pin "13") (pinfunction "VCC_13") (pintype "power_in"))
      (node (ref "2") (pin "13") (pinfunction "VCC_13") (pintype "power_in"))
      (node (ref "3") (pin "13") (pinfunction "VCC_13") (pintype "power_in"))
      (node (ref "4") (pin "13") (pinfunction "VCC_13") (pintype "power_in"))
      (node (ref "5") (pin "13") (pinfunction "VCC_13") (pintype "power_in"))
      (node (ref "6") (pin "13") (pinfunction "VCC_13") (pintype "power_in"))
      (node (ref "7") (pin "13") (pinfunction "VCC_13") (pintype "power_in"))
      (node (ref "8") (pin "13") (pinfunction "VCC_13") (pintype "power_in"))
      (node (ref "9") (pin "13") (pinfunction "VCC_13") (pintype "power_in"))
      (node (ref "C1") (pin "2") (pinfunction "2_2") (pintype "passive"))
      (node (ref "C2") (pin "1") (pinfunction "1_1") (pintype "passive"))
      (node (ref "C3") (pin "1") (pinfunction "1_1") (pintype "passive"))
      (node (ref "C4") (pin "1") (pinfunction "1_1") (pintype "passive"))
      (node (ref "C5") (pin "1") (pinfunction "1_1") (pintype "passive"))
      (node (ref "J12") (pin "4") (pinfunction "4_4") (pintype "passive"))
      (node (ref "J13") (pin "4") (pinfunction "4_4") (pintype "passive"))
      (node (ref "J19") (pin "4") (pinfunction "4_4") (pintype "passive"))
      (node (ref "J20") (pin "4") (pinfunction "4_4") (pintype "passive"))
      (node (ref "J25") (pin "4") (pinfunction "4_4") (pintype "passive"))
      (node (ref "J26") (pin "4") (pinfunction "4_4") (pintype "passive"))
      (node (ref "J32") (pin "4") (pinfunction "4_4") (pintype "passive"))
      (node (ref "J33") (pin "4") (pinfunction "4_4") (pintype "passive"))
      (node (ref "J38") (pin "4") (pinfunction "4_4") (pintype "passive"))
      (node (ref "J39") (pin "4") (pinfunction "4_4") (pintype "passive"))
      (node (ref "J44") (pin "4") (pinfunction "4_4") (pintype "passive"))
      (node (ref "J45") (pin "4") (pinfunction "4_4") (pintype "passive"))
      (node (ref "J5") (pin "4") (pinfunction "4_4") (pintype "passive"))
      (node (ref "J50") (pin "4") (pinfunction "4_4") (pintype "passive"))
      (node (ref "J51") (pin "4") (pinfunction "4_4") (pintype "passive"))
      (node (ref "J54") (pin "9") (pinfunction "9_9") (pintype "passive"))
      (node (ref "J55") (pin "9") (pinfunction "9_9") (pintype "passive"))
      (node (ref "J6") (pin "4") (pinfunction "4_4") (pintype "passive"))
    )
    (net (code "2") (name "/A0") (class "Default")
      (node (ref "J54") (pin "1") (pinfunction "1_1") (pintype "passive"))
      (node (ref "J55") (pin "1") (pinfunction "1_1") (pintype "passive"))
    )
    (net (code "3") (name "/A1") (class "Default")
      (node (ref "J54") (pin "2") (pinfunction "2_2") (pintype "passive"))
      (node (ref "J55") (pin "2") (pinfunction "2_2") (pintype "passive"))
    )
    (net (code "4") (name "/A2") (class "Default")
      (node (ref "J54") (pin "3") (pinfunction "3_3") (pintype "passive"))
      (node (ref "J55") (pin "3") (pinfunction "3_3") (pintype "passive"))
    )
    (net (code "5") (name "/A3") (class "Default")
      (node (ref "J54") (pin "4") (pinfunction "4_4") (pintype "passive"))
      (node (ref "J55") (pin "4") (pinfunction "4_4") (pintype "passive"))
    )
    (net (code "6") (name "/CLK") (class "Default")
      (node (ref "1") (pin "9") (pinfunction "CLK_9") (pintype "input"))
      (node (ref "10") (pin "9") (pinfunction "CLK_9") (pintype "input"))
      (node (ref "11") (pin "9") (pinfunction "CLK_9") (pintype "input"))
      (node (ref "12") (pin "9") (pinfunction "CLK_9") (pintype "input"))
      (node (ref "13") (pin "9") (pinfunction "CLK_9") (pintype "input"))
      (node (ref "14") (pin "9") (pinfunction "CLK_9") (pintype "input"))
      (node (ref "15") (pin "9") (pinfunction "CLK_9") (pintype "input"))
      (node (ref "16") (pin "9") (pinfunction "CLK_9") (pintype "input"))
      (node (ref "2") (pin "9") (pinfunction "CLK_9") (pintype "input"))
      (node (ref "3") (pin "9") (pinfunction "CLK_9") (pintype "input"))
      (node (ref "4") (pin "9") (pinfunction "CLK_9") (pintype "input"))
      (node (ref "5") (pin "9") (pinfunction "CLK_9") (pintype "input"))
      (node (ref "6") (pin "9") (pinfunction "CLK_9") (pintype "input"))
      (node (ref "7") (pin "9") (pinfunction "CLK_9") (pintype "input"))
      (node (ref "8") (pin "9") (pinfunction "CLK_9") (pintype "input"))
      (node (ref "9") (pin "9") (pinfunction "CLK_9") (pintype "input"))
      (node (ref "J1") (pin "9") (pinfunction "9_9") (pintype "passive"))
      (node (ref "J11") (pin "9") (pinfunction "9_9") (pintype "passive"))
      (node (ref "J15") (pin "9") (pinfunction "9_9") (pintype "passive"))
      (node (ref "J17") (pin "9") (pinfunction "9_9") (pintype "passive"))
      (node (ref "J21") (pin "9") (pinfunction "9_9") (pintype "passive"))
      (node (ref "J23") (pin "9") (pinfunction "9_9") (pintype "passive"))
      (node (ref "J28") (pin "9") (pinfunction "9_9") (pintype "passive"))
      (node (ref "J3") (pin "9") (pinfunction "9_9") (pintype "passive"))
      (node (ref "J30") (pin "9") (pinfunction "9_9") (pintype "passive"))
      (node (ref "J34") (pin "9") (pinfunction "9_9") (pintype "passive"))
      (node (ref "J36") (pin "9") (pinfunction "9_9") (pintype "passive"))
      (node (ref "J40") (pin "9") (pinfunction "9_9") (pintype "passive"))
      (node (ref "J42") (pin "9") (pinfunction "9_9") (pintype "passive"))
      (node (ref "J46") (pin "9") (pinfunction "9_9") (pintype "passive"))
      (node (ref "J48") (pin "9") (pinfunction "9_9") (pintype "passive"))
      (node (ref "J7") (pin "9") (pinfunction "9_9") (pintype "passive"))
      (node (ref "J9") (pin "9") (pinfunction "9_9") (pintype "passive"))
    )
    (net (code "7") (name "/CLR") (class "Default")
      (node (ref "1") (pin "10") (pinfunction "CLR_10") (pintype "input"))
      (node (ref "10") (pin "10") (pinfunction "CLR_10") (pintype "input"))
      (node (ref "11") (pin "10") (pinfunction "CLR_10") (pintype "input"))
      (node (ref "12") (pin "10") (pinfunction "CLR_10") (pintype "input"))
      (node (ref "13") (pin "10") (pinfunction "CLR_10") (pintype "input"))
      (node (ref "14") (pin "10") (pinfunction "CLR_10") (pintype "input"))
      (node (ref "15") (pin "10") (pinfunction "CLR_10") (pintype "input"))
      (node (ref "16") (pin "10") (pinfunction "CLR_10") (pintype "input"))
      (node (ref "2") (pin "10") (pinfunction "CLR_10") (pintype "input"))
      (node (ref "3") (pin "10") (pinfunction "CLR_10") (pintype "input"))
      (node (ref "4") (pin "10") (pinfunction "CLR_10") (pintype "input"))
      (node (ref "5") (pin "10") (pinfunction "CLR_10") (pintype "input"))
      (node (ref "6") (pin "10") (pinfunction "CLR_10") (pintype "input"))
      (node (ref "7") (pin "10") (pinfunction "CLR_10") (pintype "input"))
      (node (ref "8") (pin "10") (pinfunction "CLR_10") (pintype "input"))
      (node (ref "9") (pin "10") (pinfunction "CLR_10") (pintype "input"))
      (node (ref "J1") (pin "10") (pinfunction "10_10") (pintype "passive"))
      (node (ref "J11") (pin "10") (pinfunction "10_10") (pintype "passive"))
      (node (ref "J15") (pin "10") (pinfunction "10_10") (pintype "passive"))
      (node (ref "J17") (pin "10") (pinfunction "10_10") (pintype "passive"))
      (node (ref "J21") (pin "10") (pinfunction "10_10") (pintype "passive"))
      (node (ref "J23") (pin "10") (pinfunction "10_10") (pintype "passive"))
      (node (ref "J28") (pin "10") (pinfunction "10_10") (pintype "passive"))
      (node (ref "J3") (pin "10") (pinfunction "10_10") (pintype "passive"))
      (node (ref "J30") (pin "10") (pinfunction "10_10") (pintype "passive"))
      (node (ref "J34") (pin "10") (pinfunction "10_10") (pintype "passive"))
      (node (ref "J36") (pin "10") (pinfunction "10_10") (pintype "passive"))
      (node (ref "J40") (pin "10") (pinfunction "10_10") (pintype "passive"))
      (node (ref "J42") (pin "10") (pinfunction "10_10") (pintype "passive"))
      (node (ref "J46") (pin "10") (pinfunction "10_10") (pintype "passive"))
      (node (ref "J48") (pin "10") (pinfunction "10_10") (pintype "passive"))
      (node (ref "J7") (pin "10") (pinfunction "10_10") (pintype "passive"))
      (node (ref "J9") (pin "10") (pinfunction "10_10") (pintype "passive"))
    )
    (net (code "8") (name "/D0") (class "Default")
      (node (ref "1") (pin "1") (pinfunction "D0_1") (pintype "input"))
      (node (ref "10") (pin "1") (pinfunction "D0_1") (pintype "input"))
      (node (ref "11") (pin "1") (pinfunction "D0_1") (pintype "input"))
      (node (ref "12") (pin "1") (pinfunction "D0_1") (pintype "input"))
      (node (ref "13") (pin "1") (pinfunction "D0_1") (pintype "input"))
      (node (ref "14") (pin "1") (pinfunction "D0_1") (pintype "input"))
      (node (ref "15") (pin "1") (pinfunction "D0_1") (pintype "input"))
      (node (ref "16") (pin "1") (pinfunction "D0_1") (pintype "input"))
      (node (ref "2") (pin "1") (pinfunction "D0_1") (pintype "input"))
      (node (ref "3") (pin "1") (pinfunction "D0_1") (pintype "input"))
      (node (ref "4") (pin "1") (pinfunction "D0_1") (pintype "input"))
      (node (ref "5") (pin "1") (pinfunction "D0_1") (pintype "input"))
      (node (ref "6") (pin "1") (pinfunction "D0_1") (pintype "input"))
      (node (ref "7") (pin "1") (pinfunction "D0_1") (pintype "input"))
      (node (ref "8") (pin "1") (pinfunction "D0_1") (pintype "input"))
      (node (ref "9") (pin "1") (pinfunction "D0_1") (pintype "input"))
      (node (ref "J1") (pin "1") (pinfunction "1_1") (pintype "passive"))
      (node (ref "J11") (pin "1") (pinfunction "1_1") (pintype "passive"))
      (node (ref "J15") (pin "1") (pinfunction "1_1") (pintype "passive"))
      (node (ref "J17") (pin "1") (pinfunction "1_1") (pintype "passive"))
      (node (ref "J21") (pin "1") (pinfunction "1_1") (pintype "passive"))
      (node (ref "J23") (pin "1") (pinfunction "1_1") (pintype "passive"))
      (node (ref "J28") (pin "1") (pinfunction "1_1") (pintype "passive"))
      (node (ref "J3") (pin "1") (pinfunction "1_1") (pintype "passive"))
      (node (ref "J30") (pin "1") (pinfunction "1_1") (pintype "passive"))
      (node (ref "J34") (pin "1") (pinfunction "1_1") (pintype "passive"))
      (node (ref "J36") (pin "1") (pinfunction "1_1") (pintype "passive"))
      (node (ref "J40") (pin "1") (pinfunction "1_1") (pintype "passive"))
      (node (ref "J42") (pin "1") (pinfunction "1_1") (pintype "passive"))
      (node (ref "J46") (pin "1") (pinfunction "1_1") (pintype "passive"))
      (node (ref "J48") (pin "1") (pinfunction "1_1") (pintype "passive"))
      (node (ref "J7") (pin "1") (pinfunction "1_1") (pintype "passive"))
      (node (ref "J9") (pin "1") (pinfunction "1_1") (pintype "passive"))
    )
    (net (code "9") (name "/D1") (class "Default")
      (node (ref "1") (pin "2") (pinfunction "D1_2") (pintype "input"))
      (node (ref "10") (pin "2") (pinfunction "D1_2") (pintype "input"))
      (node (ref "11") (pin "2") (pinfunction "D1_2") (pintype "input"))
      (node (ref "12") (pin "2") (pinfunction "D1_2") (pintype "input"))
      (node (ref "13") (pin "2") (pinfunction "D1_2") (pintype "input"))
      (node (ref "14") (pin "2") (pinfunction "D1_2") (pintype "input"))
      (node (ref "15") (pin "2") (pinfunction "D1_2") (pintype "input"))
      (node (ref "16") (pin "2") (pinfunction "D1_2") (pintype "input"))
      (node (ref "2") (pin "2") (pinfunction "D1_2") (pintype "input"))
      (node (ref "3") (pin "2") (pinfunction "D1_2") (pintype "input"))
      (node (ref "4") (pin "2") (pinfunction "D1_2") (pintype "input"))
      (node (ref "5") (pin "2") (pinfunction "D1_2") (pintype "input"))
      (node (ref "6") (pin "2") (pinfunction "D1_2") (pintype "input"))
      (node (ref "7") (pin "2") (pinfunction "D1_2") (pintype "input"))
      (node (ref "8") (pin "2") (pinfunction "D1_2") (pintype "input"))
      (node (ref "9") (pin "2") (pinfunction "D1_2") (pintype "input"))
      (node (ref "J1") (pin "2") (pinfunction "2_2") (pintype "passive"))
      (node (ref "J11") (pin "2") (pinfunction "2_2") (pintype "passive"))
      (node (ref "J15") (pin "2") (pinfunction "2_2") (pintype "passive"))
      (node (ref "J17") (pin "2") (pinfunction "2_2") (pintype "passive"))
      (node (ref "J21") (pin "2") (pinfunction "2_2") (pintype "passive"))
      (node (ref "J23") (pin "2") (pinfunction "2_2") (pintype "passive"))
      (node (ref "J28") (pin "2") (pinfunction "2_2") (pintype "passive"))
      (node (ref "J3") (pin "2") (pinfunction "2_2") (pintype "passive"))
      (node (ref "J30") (pin "2") (pinfunction "2_2") (pintype "passive"))
      (node (ref "J34") (pin "2") (pinfunction "2_2") (pintype "passive"))
      (node (ref "J36") (pin "2") (pinfunction "2_2") (pintype "passive"))
      (node (ref "J40") (pin "2") (pinfunction "2_2") (pintype "passive"))
      (node (ref "J42") (pin "2") (pinfunction "2_2") (pintype "passive"))
      (node (ref "J46") (pin "2") (pinfunction "2_2") (pintype "passive"))
      (node (ref "J48") (pin "2") (pinfunction "2_2") (pintype "passive"))
      (node (ref "J7") (pin "2") (pinfunction "2_2") (pintype "passive"))
      (node (ref "J9") (pin "2") (pinfunction "2_2") (pintype "passive"))
    )
    (net (code "10") (name "/D2") (class "Default")
      (node (ref "1") (pin "3") (pinfunction "D2_3") (pintype "input"))
      (node (ref "10") (pin "3") (pinfunction "D2_3") (pintype "input"))
      (node (ref "11") (pin "3") (pinfunction "D2_3") (pintype "input"))
      (node (ref "12") (pin "3") (pinfunction "D2_3") (pintype "input"))
      (node (ref "13") (pin "3") (pinfunction "D2_3") (pintype "input"))
      (node (ref "14") (pin "3") (pinfunction "D2_3") (pintype "input"))
      (node (ref "15") (pin "3") (pinfunction "D2_3") (pintype "input"))
      (node (ref "16") (pin "3") (pinfunction "D2_3") (pintype "input"))
      (node (ref "2") (pin "3") (pinfunction "D2_3") (pintype "input"))
      (node (ref "3") (pin "3") (pinfunction "D2_3") (pintype "input"))
      (node (ref "4") (pin "3") (pinfunction "D2_3") (pintype "input"))
      (node (ref "5") (pin "3") (pinfunction "D2_3") (pintype "input"))
      (node (ref "6") (pin "3") (pinfunction "D2_3") (pintype "input"))
      (node (ref "7") (pin "3") (pinfunction "D2_3") (pintype "input"))
      (node (ref "8") (pin "3") (pinfunction "D2_3") (pintype "input"))
      (node (ref "9") (pin "3") (pinfunction "D2_3") (pintype "input"))
      (node (ref "J1") (pin "3") (pinfunction "3_3") (pintype "passive"))
      (node (ref "J11") (pin "3") (pinfunction "3_3") (pintype "passive"))
      (node (ref "J15") (pin "3") (pinfunction "3_3") (pintype "passive"))
      (node (ref "J17") (pin "3") (pinfunction "3_3") (pintype "passive"))
      (node (ref "J21") (pin "3") (pinfunction "3_3") (pintype "passive"))
      (node (ref "J23") (pin "3") (pinfunction "3_3") (pintype "passive"))
      (node (ref "J28") (pin "3") (pinfunction "3_3") (pintype "passive"))
      (node (ref "J3") (pin "3") (pinfunction "3_3") (pintype "passive"))
      (node (ref "J30") (pin "3") (pinfunction "3_3") (pintype "passive"))
      (node (ref "J34") (pin "3") (pinfunction "3_3") (pintype "passive"))
      (node (ref "J36") (pin "3") (pinfunction "3_3") (pintype "passive"))
      (node (ref "J40") (pin "3") (pinfunction "3_3") (pintype "passive"))
      (node (ref "J42") (pin "3") (pinfunction "3_3") (pintype "passive"))
      (node (ref "J46") (pin "3") (pinfunction "3_3") (pintype "passive"))
      (node (ref "J48") (pin "3") (pinfunction "3_3") (pintype "passive"))
      (node (ref "J7") (pin "3") (pinfunction "3_3") (pintype "passive"))
      (node (ref "J9") (pin "3") (pinfunction "3_3") (pintype "passive"))
    )
    (net (code "11") (name "/D3") (class "Default")
      (node (ref "1") (pin "4") (pinfunction "D3_4") (pintype "input"))
      (node (ref "10") (pin "4") (pinfunction "D3_4") (pintype "input"))
      (node (ref "11") (pin "4") (pinfunction "D3_4") (pintype "input"))
      (node (ref "12") (pin "4") (pinfunction "D3_4") (pintype "input"))
      (node (ref "13") (pin "4") (pinfunction "D3_4") (pintype "input"))
      (node (ref "14") (pin "4") (pinfunction "D3_4") (pintype "input"))
      (node (ref "15") (pin "4") (pinfunction "D3_4") (pintype "input"))
      (node (ref "16") (pin "4") (pinfunction "D3_4") (pintype "input"))
      (node (ref "2") (pin "4") (pinfunction "D3_4") (pintype "input"))
      (node (ref "3") (pin "4") (pinfunction "D3_4") (pintype "input"))
      (node (ref "4") (pin "4") (pinfunction "D3_4") (pintype "input"))
      (node (ref "5") (pin "4") (pinfunction "D3_4") (pintype "input"))
      (node (ref "6") (pin "4") (pinfunction "D3_4") (pintype "input"))
      (node (ref "7") (pin "4") (pinfunction "D3_4") (pintype "input"))
      (node (ref "8") (pin "4") (pinfunction "D3_4") (pintype "input"))
      (node (ref "9") (pin "4") (pinfunction "D3_4") (pintype "input"))
      (node (ref "J1") (pin "4") (pinfunction "4_4") (pintype "passive"))
      (node (ref "J11") (pin "4") (pinfunction "4_4") (pintype "passive"))
      (node (ref "J15") (pin "4") (pinfunction "4_4") (pintype "passive"))
      (node (ref "J17") (pin "4") (pinfunction "4_4") (pintype "passive"))
      (node (ref "J21") (pin "4") (pinfunction "4_4") (pintype "passive"))
      (node (ref "J23") (pin "4") (pinfunction "4_4") (pintype "passive"))
      (node (ref "J28") (pin "4") (pinfunction "4_4") (pintype "passive"))
      (node (ref "J3") (pin "4") (pinfunction "4_4") (pintype "passive"))
      (node (ref "J30") (pin "4") (pinfunction "4_4") (pintype "passive"))
      (node (ref "J34") (pin "4") (pinfunction "4_4") (pintype "passive"))
      (node (ref "J36") (pin "4") (pinfunction "4_4") (pintype "passive"))
      (node (ref "J40") (pin "4") (pinfunction "4_4") (pintype "passive"))
      (node (ref "J42") (pin "4") (pinfunction "4_4") (pintype "passive"))
      (node (ref "J46") (pin "4") (pinfunction "4_4") (pintype "passive"))
      (node (ref "J48") (pin "4") (pinfunction "4_4") (pintype "passive"))
      (node (ref "J7") (pin "4") (pinfunction "4_4") (pintype "passive"))
      (node (ref "J9") (pin "4") (pinfunction "4_4") (pintype "passive"))
    )
    (net (code "12") (name "/D4") (class "Default")
      (node (ref "1") (pin "5") (pinfunction "D4_5") (pintype "input"))
      (node (ref "10") (pin "5") (pinfunction "D4_5") (pintype "input"))
      (node (ref "11") (pin "5") (pinfunction "D4_5") (pintype "input"))
      (node (ref "12") (pin "5") (pinfunction "D4_5") (pintype "input"))
      (node (ref "13") (pin "5") (pinfunction "D4_5") (pintype "input"))
      (node (ref "14") (pin "5") (pinfunction "D4_5") (pintype "input"))
      (node (ref "15") (pin "5") (pinfunction "D4_5") (pintype "input"))
      (node (ref "16") (pin "5") (pinfunction "D4_5") (pintype "input"))
      (node (ref "2") (pin "5") (pinfunction "D4_5") (pintype "input"))
      (node (ref "3") (pin "5") (pinfunction "D4_5") (pintype "input"))
      (node (ref "4") (pin "5") (pinfunction "D4_5") (pintype "input"))
      (node (ref "5") (pin "5") (pinfunction "D4_5") (pintype "input"))
      (node (ref "6") (pin "5") (pinfunction "D4_5") (pintype "input"))
      (node (ref "7") (pin "5") (pinfunction "D4_5") (pintype "input"))
      (node (ref "8") (pin "5") (pinfunction "D4_5") (pintype "input"))
      (node (ref "9") (pin "5") (pinfunction "D4_5") (pintype "input"))
      (node (ref "J1") (pin "5") (pinfunction "5_5") (pintype "passive"))
      (node (ref "J11") (pin "5") (pinfunction "5_5") (pintype "passive"))
      (node (ref "J15") (pin "5") (pinfunction "5_5") (pintype "passive"))
      (node (ref "J17") (pin "5") (pinfunction "5_5") (pintype "passive"))
      (node (ref "J21") (pin "5") (pinfunction "5_5") (pintype "passive"))
      (node (ref "J23") (pin "5") (pinfunction "5_5") (pintype "passive"))
      (node (ref "J28") (pin "5") (pinfunction "5_5") (pintype "passive"))
      (node (ref "J3") (pin "5") (pinfunction "5_5") (pintype "passive"))
      (node (ref "J30") (pin "5") (pinfunction "5_5") (pintype "passive"))
      (node (ref "J34") (pin "5") (pinfunction "5_5") (pintype "passive"))
      (node (ref "J36") (pin "5") (pinfunction "5_5") (pintype "passive"))
      (node (ref "J40") (pin "5") (pinfunction "5_5") (pintype "passive"))
      (node (ref "J42") (pin "5") (pinfunction "5_5") (pintype "passive"))
      (node (ref "J46") (pin "5") (pinfunction "5_5") (pintype "passive"))
      (node (ref "J48") (pin "5") (pinfunction "5_5") (pintype "passive"))
      (node (ref "J7") (pin "5") (pinfunction "5_5") (pintype "passive"))
      (node (ref "J9") (pin "5") (pinfunction "5_5") (pintype "passive"))
    )
    (net (code "13") (name "/D5") (class "Default")
      (node (ref "1") (pin "6") (pinfunction "D5_6") (pintype "input"))
      (node (ref "10") (pin "6") (pinfunction "D5_6") (pintype "input"))
      (node (ref "11") (pin "6") (pinfunction "D5_6") (pintype "input"))
      (node (ref "12") (pin "6") (pinfunction "D5_6") (pintype "input"))
      (node (ref "13") (pin "6") (pinfunction "D5_6") (pintype "input"))
      (node (ref "14") (pin "6") (pinfunction "D5_6") (pintype "input"))
      (node (ref "15") (pin "6") (pinfunction "D5_6") (pintype "input"))
      (node (ref "16") (pin "6") (pinfunction "D5_6") (pintype "input"))
      (node (ref "2") (pin "6") (pinfunction "D5_6") (pintype "input"))
      (node (ref "3") (pin "6") (pinfunction "D5_6") (pintype "input"))
      (node (ref "4") (pin "6") (pinfunction "D5_6") (pintype "input"))
      (node (ref "5") (pin "6") (pinfunction "D5_6") (pintype "input"))
      (node (ref "6") (pin "6") (pinfunction "D5_6") (pintype "input"))
      (node (ref "7") (pin "6") (pinfunction "D5_6") (pintype "input"))
      (node (ref "8") (pin "6") (pinfunction "D5_6") (pintype "input"))
      (node (ref "9") (pin "6") (pinfunction "D5_6") (pintype "input"))
      (node (ref "J1") (pin "6") (pinfunction "6_6") (pintype "passive"))
      (node (ref "J11") (pin "6") (pinfunction "6_6") (pintype "passive"))
      (node (ref "J15") (pin "6") (pinfunction "6_6") (pintype "passive"))
      (node (ref "J17") (pin "6") (pinfunction "6_6") (pintype "passive"))
      (node (ref "J21") (pin "6") (pinfunction "6_6") (pintype "passive"))
      (node (ref "J23") (pin "6") (pinfunction "6_6") (pintype "passive"))
      (node (ref "J28") (pin "6") (pinfunction "6_6") (pintype "passive"))
      (node (ref "J3") (pin "6") (pinfunction "6_6") (pintype "passive"))
      (node (ref "J30") (pin "6") (pinfunction "6_6") (pintype "passive"))
      (node (ref "J34") (pin "6") (pinfunction "6_6") (pintype "passive"))
      (node (ref "J36") (pin "6") (pinfunction "6_6") (pintype "passive"))
      (node (ref "J40") (pin "6") (pinfunction "6_6") (pintype "passive"))
      (node (ref "J42") (pin "6") (pinfunction "6_6") (pintype "passive"))
      (node (ref "J46") (pin "6") (pinfunction "6_6") (pintype "passive"))
      (node (ref "J48") (pin "6") (pinfunction "6_6") (pintype "passive"))
      (node (ref "J7") (pin "6") (pinfunction "6_6") (pintype "passive"))
      (node (ref "J9") (pin "6") (pinfunction "6_6") (pintype "passive"))
    )
    (net (code "14") (name "/D6") (class "Default")
      (node (ref "1") (pin "7") (pinfunction "D6_7") (pintype "input"))
      (node (ref "10") (pin "7") (pinfunction "D6_7") (pintype "input"))
      (node (ref "11") (pin "7") (pinfunction "D6_7") (pintype "input"))
      (node (ref "12") (pin "7") (pinfunction "D6_7") (pintype "input"))
      (node (ref "13") (pin "7") (pinfunction "D6_7") (pintype "input"))
      (node (ref "14") (pin "7") (pinfunction "D6_7") (pintype "input"))
      (node (ref "15") (pin "7") (pinfunction "D6_7") (pintype "input"))
      (node (ref "16") (pin "7") (pinfunction "D6_7") (pintype "input"))
      (node (ref "2") (pin "7") (pinfunction "D6_7") (pintype "input"))
      (node (ref "3") (pin "7") (pinfunction "D6_7") (pintype "input"))
      (node (ref "4") (pin "7") (pinfunction "D6_7") (pintype "input"))
      (node (ref "5") (pin "7") (pinfunction "D6_7") (pintype "input"))
      (node (ref "6") (pin "7") (pinfunction "D6_7") (pintype "input"))
      (node (ref "7") (pin "7") (pinfunction "D6_7") (pintype "input"))
      (node (ref "8") (pin "7") (pinfunction "D6_7") (pintype "input"))
      (node (ref "9") (pin "7") (pinfunction "D6_7") (pintype "input"))
      (node (ref "J1") (pin "7") (pinfunction "7_7") (pintype "passive"))
      (node (ref "J11") (pin "7") (pinfunction "7_7") (pintype "passive"))
      (node (ref "J15") (pin "7") (pinfunction "7_7") (pintype "passive"))
      (node (ref "J17") (pin "7") (pinfunction "7_7") (pintype "passive"))
      (node (ref "J21") (pin "7") (pinfunction "7_7") (pintype "passive"))
      (node (ref "J23") (pin "7") (pinfunction "7_7") (pintype "passive"))
      (node (ref "J28") (pin "7") (pinfunction "7_7") (pintype "passive"))
      (node (ref "J3") (pin "7") (pinfunction "7_7") (pintype "passive"))
      (node (ref "J30") (pin "7") (pinfunction "7_7") (pintype "passive"))
      (node (ref "J34") (pin "7") (pinfunction "7_7") (pintype "passive"))
      (node (ref "J36") (pin "7") (pinfunction "7_7") (pintype "passive"))
      (node (ref "J40") (pin "7") (pinfunction "7_7") (pintype "passive"))
      (node (ref "J42") (pin "7") (pinfunction "7_7") (pintype "passive"))
      (node (ref "J46") (pin "7") (pinfunction "7_7") (pintype "passive"))
      (node (ref "J48") (pin "7") (pinfunction "7_7") (pintype "passive"))
      (node (ref "J7") (pin "7") (pinfunction "7_7") (pintype "passive"))
      (node (ref "J9") (pin "7") (pinfunction "7_7") (pintype "passive"))
    )
    (net (code "15") (name "/D7") (class "Default")
      (node (ref "1") (pin "8") (pinfunction "D7_8") (pintype "input"))
      (node (ref "10") (pin "8") (pinfunction "D7_8") (pintype "input"))
      (node (ref "11") (pin "8") (pinfunction "D7_8") (pintype "input"))
      (node (ref "12") (pin "8") (pinfunction "D7_8") (pintype "input"))
      (node (ref "13") (pin "8") (pinfunction "D7_8") (pintype "input"))
      (node (ref "14") (pin "8") (pinfunction "D7_8") (pintype "input"))
      (node (ref "15") (pin "8") (pinfunction "D7_8") (pintype "input"))
      (node (ref "16") (pin "8") (pinfunction "D7_8") (pintype "input"))
      (node (ref "2") (pin "8") (pinfunction "D7_8") (pintype "input"))
      (node (ref "3") (pin "8") (pinfunction "D7_8") (pintype "input"))
      (node (ref "4") (pin "8") (pinfunction "D7_8") (pintype "input"))
      (node (ref "5") (pin "8") (pinfunction "D7_8") (pintype "input"))
      (node (ref "6") (pin "8") (pinfunction "D7_8") (pintype "input"))
      (node (ref "7") (pin "8") (pinfunction "D7_8") (pintype "input"))
      (node (ref "8") (pin "8") (pinfunction "D7_8") (pintype "input"))
      (node (ref "9") (pin "8") (pinfunction "D7_8") (pintype "input"))
      (node (ref "J1") (pin "8") (pinfunction "8_8") (pintype "passive"))
      (node (ref "J11") (pin "8") (pinfunction "8_8") (pintype "passive"))
      (node (ref "J15") (pin "8") (pinfunction "8_8") (pintype "passive"))
      (node (ref "J17") (pin "8") (pinfunction "8_8") (pintype "passive"))
      (node (ref "J21") (pin "8") (pinfunction "8_8") (pintype "passive"))
      (node (ref "J23") (pin "8") (pinfunction "8_8") (pintype "passive"))
      (node (ref "J28") (pin "8") (pinfunction "8_8") (pintype "passive"))
      (node (ref "J3") (pin "8") (pinfunction "8_8") (pintype "passive"))
      (node (ref "J30") (pin "8") (pinfunction "8_8") (pintype "passive"))
      (node (ref "J34") (pin "8") (pinfunction "8_8") (pintype "passive"))
      (node (ref "J36") (pin "8") (pinfunction "8_8") (pintype "passive"))
      (node (ref "J40") (pin "8") (pinfunction "8_8") (pintype "passive"))
      (node (ref "J42") (pin "8") (pinfunction "8_8") (pintype "passive"))
      (node (ref "J46") (pin "8") (pinfunction "8_8") (pintype "passive"))
      (node (ref "J48") (pin "8") (pinfunction "8_8") (pintype "passive"))
      (node (ref "J7") (pin "8") (pinfunction "8_8") (pintype "passive"))
      (node (ref "J9") (pin "8") (pinfunction "8_8") (pintype "passive"))
    )
    (net (code "16") (name "/Q0") (class "Default")
      (node (ref "1") (pin "24") (pinfunction "Q0_24") (pintype "output"))
      (node (ref "10") (pin "24") (pinfunction "Q0_24") (pintype "output"))
      (node (ref "11") (pin "24") (pinfunction "Q0_24") (pintype "output"))
      (node (ref "12") (pin "24") (pinfunction "Q0_24") (pintype "output"))
      (node (ref "13") (pin "24") (pinfunction "Q0_24") (pintype "output"))
      (node (ref "14") (pin "24") (pinfunction "Q0_24") (pintype "output"))
      (node (ref "15") (pin "24") (pinfunction "Q0_24") (pintype "output"))
      (node (ref "16") (pin "24") (pinfunction "Q0_24") (pintype "output"))
      (node (ref "2") (pin "24") (pinfunction "Q0_24") (pintype "output"))
      (node (ref "3") (pin "24") (pinfunction "Q0_24") (pintype "output"))
      (node (ref "4") (pin "24") (pinfunction "Q0_24") (pintype "output"))
      (node (ref "5") (pin "24") (pinfunction "Q0_24") (pintype "output"))
      (node (ref "6") (pin "24") (pinfunction "Q0_24") (pintype "output"))
      (node (ref "7") (pin "24") (pinfunction "Q0_24") (pintype "output"))
      (node (ref "8") (pin "24") (pinfunction "Q0_24") (pintype "output"))
      (node (ref "9") (pin "24") (pinfunction "Q0_24") (pintype "output"))
      (node (ref "J10") (pin "1") (pinfunction "1_1") (pintype "passive"))
      (node (ref "J16") (pin "1") (pinfunction "1_1") (pintype "passive"))
      (node (ref "J18") (pin "1") (pinfunction "1_1") (pintype "passive"))
      (node (ref "J2") (pin "1") (pinfunction "1_1") (pintype "passive"))
      (node (ref "J22") (pin "1") (pinfunction "1_1") (pintype "passive"))
      (node (ref "J24") (pin "1") (pinfunction "1_1") (pintype "passive"))
      (node (ref "J27") (pin "1") (pinfunction "1_1") (pintype "passive"))
      (node (ref "J29") (pin "1") (pinfunction "1_1") (pintype "passive"))
      (node (ref "J31") (pin "1") (pinfunction "1_1") (pintype "passive"))
      (node (ref "J35") (pin "1") (pinfunction "1_1") (pintype "passive"))
      (node (ref "J37") (pin "1") (pinfunction "1_1") (pintype "passive"))
      (node (ref "J4") (pin "1") (pinfunction "1_1") (pintype "passive"))
      (node (ref "J41") (pin "1") (pinfunction "1_1") (pintype "passive"))
      (node (ref "J43") (pin "1") (pinfunction "1_1") (pintype "passive"))
      (node (ref "J47") (pin "1") (pinfunction "1_1") (pintype "passive"))
      (node (ref "J49") (pin "1") (pinfunction "1_1") (pintype "passive"))
      (node (ref "J8") (pin "1") (pinfunction "1_1") (pintype "passive"))
      (node (ref "R1") (pin "1") (pinfunction "1_1") (pintype "passive"))
    )
    (net (code "17") (name "/Q1") (class "Default")
      (node (ref "1") (pin "23") (pinfunction "Q1_23") (pintype "output"))
      (node (ref "10") (pin "23") (pinfunction "Q1_23") (pintype "output"))
      (node (ref "11") (pin "23") (pinfunction "Q1_23") (pintype "output"))
      (node (ref "12") (pin "23") (pinfunction "Q1_23") (pintype "output"))
      (node (ref "13") (pin "23") (pinfunction "Q1_23") (pintype "output"))
      (node (ref "14") (pin "23") (pinfunction "Q1_23") (pintype "output"))
      (node (ref "15") (pin "23") (pinfunction "Q1_23") (pintype "output"))
      (node (ref "16") (pin "23") (pinfunction "Q1_23") (pintype "output"))
      (node (ref "2") (pin "23") (pinfunction "Q1_23") (pintype "output"))
      (node (ref "3") (pin "23") (pinfunction "Q1_23") (pintype "output"))
      (node (ref "4") (pin "23") (pinfunction "Q1_23") (pintype "output"))
      (node (ref "5") (pin "23") (pinfunction "Q1_23") (pintype "output"))
      (node (ref "6") (pin "23") (pinfunction "Q1_23") (pintype "output"))
      (node (ref "7") (pin "23") (pinfunction "Q1_23") (pintype "output"))
      (node (ref "8") (pin "23") (pinfunction "Q1_23") (pintype "output"))
      (node (ref "9") (pin "23") (pinfunction "Q1_23") (pintype "output"))
      (node (ref "J10") (pin "2") (pinfunction "2_2") (pintype "passive"))
      (node (ref "J16") (pin "2") (pinfunction "2_2") (pintype "passive"))
      (node (ref "J18") (pin "2") (pinfunction "2_2") (pintype "passive"))
      (node (ref "J2") (pin "2") (pinfunction "2_2") (pintype "passive"))
      (node (ref "J22") (pin "2") (pinfunction "2_2") (pintype "passive"))
      (node (ref "J24") (pin "2") (pinfunction "2_2") (pintype "passive"))
      (node (ref "J27") (pin "2") (pinfunction "2_2") (pintype "passive"))
      (node (ref "J29") (pin "2") (pinfunction "2_2") (pintype "passive"))
      (node (ref "J31") (pin "2") (pinfunction "2_2") (pintype "passive"))
      (node (ref "J35") (pin "2") (pinfunction "2_2") (pintype "passive"))
      (node (ref "J37") (pin "2") (pinfunction "2_2") (pintype "passive"))
      (node (ref "J4") (pin "2") (pinfunction "2_2") (pintype "passive"))
      (node (ref "J41") (pin "2") (pinfunction "2_2") (pintype "passive"))
      (node (ref "J43") (pin "2") (pinfunction "2_2") (pintype "passive"))
      (node (ref "J47") (pin "2") (pinfunction "2_2") (pintype "passive"))
      (node (ref "J49") (pin "2") (pinfunction "2_2") (pintype "passive"))
      (node (ref "J8") (pin "2") (pinfunction "2_2") (pintype "passive"))
      (node (ref "R2") (pin "1") (pinfunction "1_1") (pintype "passive"))
    )
    (net (code "18") (name "/Q2") (class "Default")
      (node (ref "1") (pin "22") (pinfunction "Q2_22") (pintype "output"))
      (node (ref "10") (pin "22") (pinfunction "Q2_22") (pintype "output"))
      (node (ref "11") (pin "22") (pinfunction "Q2_22") (pintype "output"))
      (node (ref "12") (pin "22") (pinfunction "Q2_22") (pintype "output"))
      (node (ref "13") (pin "22") (pinfunction "Q2_22") (pintype "output"))
      (node (ref "14") (pin "22") (pinfunction "Q2_22") (pintype "output"))
      (node (ref "15") (pin "22") (pinfunction "Q2_22") (pintype "output"))
      (node (ref "16") (pin "22") (pinfunction "Q2_22") (pintype "output"))
      (node (ref "2") (pin "22") (pinfunction "Q2_22") (pintype "output"))
      (node (ref "3") (pin "22") (pinfunction "Q2_22") (pintype "output"))
      (node (ref "4") (pin "22") (pinfunction "Q2_22") (pintype "output"))
      (node (ref "5") (pin "22") (pinfunction "Q2_22") (pintype "output"))
      (node (ref "6") (pin "22") (pinfunction "Q2_22") (pintype "output"))
      (node (ref "7") (pin "22") (pinfunction "Q2_22") (pintype "output"))
      (node (ref "8") (pin "22") (pinfunction "Q2_22") (pintype "output"))
      (node (ref "9") (pin "22") (pinfunction "Q2_22") (pintype "output"))
      (node (ref "J10") (pin "3") (pinfunction "3_3") (pintype "passive"))
      (node (ref "J16") (pin "3") (pinfunction "3_3") (pintype "passive"))
      (node (ref "J18") (pin "3") (pinfunction "3_3") (pintype "passive"))
      (node (ref "J2") (pin "3") (pinfunction "3_3") (pintype "passive"))
      (node (ref "J22") (pin "3") (pinfunction "3_3") (pintype "passive"))
      (node (ref "J24") (pin "3") (pinfunction "3_3") (pintype "passive"))
      (node (ref "J27") (pin "3") (pinfunction "3_3") (pintype "passive"))
      (node (ref "J29") (pin "3") (pinfunction "3_3") (pintype "passive"))
      (node (ref "J31") (pin "3") (pinfunction "3_3") (pintype "passive"))
      (node (ref "J35") (pin "3") (pinfunction "3_3") (pintype "passive"))
      (node (ref "J37") (pin "3") (pinfunction "3_3") (pintype "passive"))
      (node (ref "J4") (pin "3") (pinfunction "3_3") (pintype "passive"))
      (node (ref "J41") (pin "3") (pinfunction "3_3") (pintype "passive"))
      (node (ref "J43") (pin "3") (pinfunction "3_3") (pintype "passive"))
      (node (ref "J47") (pin "3") (pinfunction "3_3") (pintype "passive"))
      (node (ref "J49") (pin "3") (pinfunction "3_3") (pintype "passive"))
      (node (ref "J8") (pin "3") (pinfunction "3_3") (pintype "passive"))
      (node (ref "R3") (pin "1") (pinfunction "1_1") (pintype "passive"))
    )
    (net (code "19") (name "/Q3") (class "Default")
      (node (ref "1") (pin "21") (pinfunction "Q3_21") (pintype "output"))
      (node (ref "10") (pin "21") (pinfunction "Q3_21") (pintype "output"))
      (node (ref "11") (pin "21") (pinfunction "Q3_21") (pintype "output"))
      (node (ref "12") (pin "21") (pinfunction "Q3_21") (pintype "output"))
      (node (ref "13") (pin "21") (pinfunction "Q3_21") (pintype "output"))
      (node (ref "14") (pin "21") (pinfunction "Q3_21") (pintype "output"))
      (node (ref "15") (pin "21") (pinfunction "Q3_21") (pintype "output"))
      (node (ref "16") (pin "21") (pinfunction "Q3_21") (pintype "output"))
      (node (ref "2") (pin "21") (pinfunction "Q3_21") (pintype "output"))
      (node (ref "3") (pin "21") (pinfunction "Q3_21") (pintype "output"))
      (node (ref "4") (pin "21") (pinfunction "Q3_21") (pintype "output"))
      (node (ref "5") (pin "21") (pinfunction "Q3_21") (pintype "output"))
      (node (ref "6") (pin "21") (pinfunction "Q3_21") (pintype "output"))
      (node (ref "7") (pin "21") (pinfunction "Q3_21") (pintype "output"))
      (node (ref "8") (pin "21") (pinfunction "Q3_21") (pintype "output"))
      (node (ref "9") (pin "21") (pinfunction "Q3_21") (pintype "output"))
      (node (ref "J10") (pin "4") (pinfunction "4_4") (pintype "passive"))
      (node (ref "J16") (pin "4") (pinfunction "4_4") (pintype "passive"))
      (node (ref "J18") (pin "4") (pinfunction "4_4") (pintype "passive"))
      (node (ref "J2") (pin "4") (pinfunction "4_4") (pintype "passive"))
      (node (ref "J22") (pin "4") (pinfunction "4_4") (pintype "passive"))
      (node (ref "J24") (pin "4") (pinfunction "4_4") (pintype "passive"))
      (node (ref "J27") (pin "4") (pinfunction "4_4") (pintype "passive"))
      (node (ref "J29") (pin "4") (pinfunction "4_4") (pintype "passive"))
      (node (ref "J31") (pin "4") (pinfunction "4_4") (pintype "passive"))
      (node (ref "J35") (pin "4") (pinfunction "4_4") (pintype "passive"))
      (node (ref "J37") (pin "4") (pinfunction "4_4") (pintype "passive"))
      (node (ref "J4") (pin "4") (pinfunction "4_4") (pintype "passive"))
      (node (ref "J41") (pin "4") (pinfunction "4_4") (pintype "passive"))
      (node (ref "J43") (pin "4") (pinfunction "4_4") (pintype "passive"))
      (node (ref "J47") (pin "4") (pinfunction "4_4") (pintype "passive"))
      (node (ref "J49") (pin "4") (pinfunction "4_4") (pintype "passive"))
      (node (ref "J8") (pin "4") (pinfunction "4_4") (pintype "passive"))
      (node (ref "R4") (pin "1") (pinfunction "1_1") (pintype "passive"))
    )
    (net (code "20") (name "/Q4") (class "Default")
      (node (ref "1") (pin "20") (pinfunction "Q4_20") (pintype "output"))
      (node (ref "10") (pin "20") (pinfunction "Q4_20") (pintype "output"))
      (node (ref "11") (pin "20") (pinfunction "Q4_20") (pintype "output"))
      (node (ref "12") (pin "20") (pinfunction "Q4_20") (pintype "output"))
      (node (ref "13") (pin "20") (pinfunction "Q4_20") (pintype "output"))
      (node (ref "14") (pin "20") (pinfunction "Q4_20") (pintype "output"))
      (node (ref "15") (pin "20") (pinfunction "Q4_20") (pintype "output"))
      (node (ref "16") (pin "20") (pinfunction "Q4_20") (pintype "output"))
      (node (ref "2") (pin "20") (pinfunction "Q4_20") (pintype "output"))
      (node (ref "3") (pin "20") (pinfunction "Q4_20") (pintype "output"))
      (node (ref "4") (pin "20") (pinfunction "Q4_20") (pintype "output"))
      (node (ref "5") (pin "20") (pinfunction "Q4_20") (pintype "output"))
      (node (ref "6") (pin "20") (pinfunction "Q4_20") (pintype "output"))
      (node (ref "7") (pin "20") (pinfunction "Q4_20") (pintype "output"))
      (node (ref "8") (pin "20") (pinfunction "Q4_20") (pintype "output"))
      (node (ref "9") (pin "20") (pinfunction "Q4_20") (pintype "output"))
      (node (ref "J10") (pin "5") (pinfunction "5_5") (pintype "passive"))
      (node (ref "J16") (pin "5") (pinfunction "5_5") (pintype "passive"))
      (node (ref "J18") (pin "5") (pinfunction "5_5") (pintype "passive"))
      (node (ref "J2") (pin "5") (pinfunction "5_5") (pintype "passive"))
      (node (ref "J22") (pin "5") (pinfunction "5_5") (pintype "passive"))
      (node (ref "J24") (pin "5") (pinfunction "5_5") (pintype "passive"))
      (node (ref "J27") (pin "5") (pinfunction "5_5") (pintype "passive"))
      (node (ref "J29") (pin "5") (pinfunction "5_5") (pintype "passive"))
      (node (ref "J31") (pin "5") (pinfunction "5_5") (pintype "passive"))
      (node (ref "J35") (pin "5") (pinfunction "5_5") (pintype "passive"))
      (node (ref "J37") (pin "5") (pinfunction "5_5") (pintype "passive"))
      (node (ref "J4") (pin "5") (pinfunction "5_5") (pintype "passive"))
      (node (ref "J41") (pin "5") (pinfunction "5_5") (pintype "passive"))
      (node (ref "J43") (pin "5") (pinfunction "5_5") (pintype "passive"))
      (node (ref "J47") (pin "5") (pinfunction "5_5") (pintype "passive"))
      (node (ref "J49") (pin "5") (pinfunction "5_5") (pintype "passive"))
      (node (ref "J8") (pin "5") (pinfunction "5_5") (pintype "passive"))
      (node (ref "R5") (pin "1") (pinfunction "1_1") (pintype "passive"))
    )
    (net (code "21") (name "/Q5") (class "Default")
      (node (ref "1") (pin "19") (pinfunction "Q5_19") (pintype "output"))
      (node (ref "10") (pin "19") (pinfunction "Q5_19") (pintype "output"))
      (node (ref "11") (pin "19") (pinfunction "Q5_19") (pintype "output"))
      (node (ref "12") (pin "19") (pinfunction "Q5_19") (pintype "output"))
      (node (ref "13") (pin "19") (pinfunction "Q5_19") (pintype "output"))
      (node (ref "14") (pin "19") (pinfunction "Q5_19") (pintype "output"))
      (node (ref "15") (pin "19") (pinfunction "Q5_19") (pintype "output"))
      (node (ref "16") (pin "19") (pinfunction "Q5_19") (pintype "output"))
      (node (ref "2") (pin "19") (pinfunction "Q5_19") (pintype "output"))
      (node (ref "3") (pin "19") (pinfunction "Q5_19") (pintype "output"))
      (node (ref "4") (pin "19") (pinfunction "Q5_19") (pintype "output"))
      (node (ref "5") (pin "19") (pinfunction "Q5_19") (pintype "output"))
      (node (ref "6") (pin "19") (pinfunction "Q5_19") (pintype "output"))
      (node (ref "7") (pin "19") (pinfunction "Q5_19") (pintype "output"))
      (node (ref "8") (pin "19") (pinfunction "Q5_19") (pintype "output"))
      (node (ref "9") (pin "19") (pinfunction "Q5_19") (pintype "output"))
      (node (ref "J10") (pin "6") (pinfunction "6_6") (pintype "passive"))
      (node (ref "J16") (pin "6") (pinfunction "6_6") (pintype "passive"))
      (node (ref "J18") (pin "6") (pinfunction "6_6") (pintype "passive"))
      (node (ref "J2") (pin "6") (pinfunction "6_6") (pintype "passive"))
      (node (ref "J22") (pin "6") (pinfunction "6_6") (pintype "passive"))
      (node (ref "J24") (pin "6") (pinfunction "6_6") (pintype "passive"))
      (node (ref "J27") (pin "6") (pinfunction "6_6") (pintype "passive"))
      (node (ref "J29") (pin "6") (pinfunction "6_6") (pintype "passive"))
      (node (ref "J31") (pin "6") (pinfunction "6_6") (pintype "passive"))
      (node (ref "J35") (pin "6") (pinfunction "6_6") (pintype "passive"))
      (node (ref "J37") (pin "6") (pinfunction "6_6") (pintype "passive"))
      (node (ref "J4") (pin "6") (pinfunction "6_6") (pintype "passive"))
      (node (ref "J41") (pin "6") (pinfunction "6_6") (pintype "passive"))
      (node (ref "J43") (pin "6") (pinfunction "6_6") (pintype "passive"))
      (node (ref "J47") (pin "6") (pinfunction "6_6") (pintype "passive"))
      (node (ref "J49") (pin "6") (pinfunction "6_6") (pintype "passive"))
      (node (ref "J8") (pin "6") (pinfunction "6_6") (pintype "passive"))
      (node (ref "R6") (pin "1") (pinfunction "1_1") (pintype "passive"))
    )
    (net (code "22") (name "/Q6") (class "Default")
      (node (ref "1") (pin "18") (pinfunction "Q6_18") (pintype "output"))
      (node (ref "10") (pin "18") (pinfunction "Q6_18") (pintype "output"))
      (node (ref "11") (pin "18") (pinfunction "Q6_18") (pintype "output"))
      (node (ref "12") (pin "18") (pinfunction "Q6_18") (pintype "output"))
      (node (ref "13") (pin "18") (pinfunction "Q6_18") (pintype "output"))
      (node (ref "14") (pin "18") (pinfunction "Q6_18") (pintype "output"))
      (node (ref "15") (pin "18") (pinfunction "Q6_18") (pintype "output"))
      (node (ref "16") (pin "18") (pinfunction "Q6_18") (pintype "output"))
      (node (ref "2") (pin "18") (pinfunction "Q6_18") (pintype "output"))
      (node (ref "3") (pin "18") (pinfunction "Q6_18") (pintype "output"))
      (node (ref "4") (pin "18") (pinfunction "Q6_18") (pintype "output"))
      (node (ref "5") (pin "18") (pinfunction "Q6_18") (pintype "output"))
      (node (ref "6") (pin "18") (pinfunction "Q6_18") (pintype "output"))
      (node (ref "7") (pin "18") (pinfunction "Q6_18") (pintype "output"))
      (node (ref "8") (pin "18") (pinfunction "Q6_18") (pintype "output"))
      (node (ref "9") (pin "18") (pinfunction "Q6_18") (pintype "output"))
      (node (ref "J10") (pin "7") (pinfunction "7_7") (pintype "passive"))
      (node (ref "J16") (pin "7") (pinfunction "7_7") (pintype "passive"))
      (node (ref "J18") (pin "7") (pinfunction "7_7") (pintype "passive"))
      (node (ref "J2") (pin "7") (pinfunction "7_7") (pintype "passive"))
      (node (ref "J22") (pin "7") (pinfunction "7_7") (pintype "passive"))
      (node (ref "J24") (pin "7") (pinfunction "7_7") (pintype "passive"))
      (node (ref "J27") (pin "7") (pinfunction "7_7") (pintype "passive"))
      (node (ref "J29") (pin "7") (pinfunction "7_7") (pintype "passive"))
      (node (ref "J31") (pin "7") (pinfunction "7_7") (pintype "passive"))
      (node (ref "J35") (pin "7") (pinfunction "7_7") (pintype "passive"))
      (node (ref "J37") (pin "7") (pinfunction "7_7") (pintype "passive"))
      (node (ref "J4") (pin "7") (pinfunction "7_7") (pintype "passive"))
      (node (ref "J41") (pin "7") (pinfunction "7_7") (pintype "passive"))
      (node (ref "J43") (pin "7") (pinfunction "7_7") (pintype "passive"))
      (node (ref "J47") (pin "7") (pinfunction "7_7") (pintype "passive"))
      (node (ref "J49") (pin "7") (pinfunction "7_7") (pintype "passive"))
      (node (ref "J8") (pin "7") (pinfunction "7_7") (pintype "passive"))
      (node (ref "R7") (pin "1") (pinfunction "1_1") (pintype "passive"))
    )
    (net (code "23") (name "/Q7") (class "Default")
      (node (ref "1") (pin "17") (pinfunction "Q7_17") (pintype "output"))
      (node (ref "10") (pin "17") (pinfunction "Q7_17") (pintype "output"))
      (node (ref "11") (pin "17") (pinfunction "Q7_17") (pintype "output"))
      (node (ref "12") (pin "17") (pinfunction "Q7_17") (pintype "output"))
      (node (ref "13") (pin "17") (pinfunction "Q7_17") (pintype "output"))
      (node (ref "14") (pin "17") (pinfunction "Q7_17") (pintype "output"))
      (node (ref "15") (pin "17") (pinfunction "Q7_17") (pintype "output"))
      (node (ref "16") (pin "17") (pinfunction "Q7_17") (pintype "output"))
      (node (ref "2") (pin "17") (pinfunction "Q7_17") (pintype "output"))
      (node (ref "3") (pin "17") (pinfunction "Q7_17") (pintype "output"))
      (node (ref "4") (pin "17") (pinfunction "Q7_17") (pintype "output"))
      (node (ref "5") (pin "17") (pinfunction "Q7_17") (pintype "output"))
      (node (ref "6") (pin "17") (pinfunction "Q7_17") (pintype "output"))
      (node (ref "7") (pin "17") (pinfunction "Q7_17") (pintype "output"))
      (node (ref "8") (pin "17") (pinfunction "Q7_17") (pintype "output"))
      (node (ref "9") (pin "17") (pinfunction "Q7_17") (pintype "output"))
      (node (ref "J10") (pin "8") (pinfunction "8_8") (pintype "passive"))
      (node (ref "J16") (pin "8") (pinfunction "8_8") (pintype "passive"))
      (node (ref "J18") (pin "8") (pinfunction "8_8") (pintype "passive"))
      (node (ref "J2") (pin "8") (pinfunction "8_8") (pintype "passive"))
      (node (ref "J22") (pin "8") (pinfunction "8_8") (pintype "passive"))
      (node (ref "J24") (pin "8") (pinfunction "8_8") (pintype "passive"))
      (node (ref "J27") (pin "8") (pinfunction "8_8") (pintype "passive"))
      (node (ref "J29") (pin "8") (pinfunction "8_8") (pintype "passive"))
      (node (ref "J31") (pin "8") (pinfunction "8_8") (pintype "passive"))
      (node (ref "J35") (pin "8") (pinfunction "8_8") (pintype "passive"))
      (node (ref "J37") (pin "8") (pinfunction "8_8") (pintype "passive"))
      (node (ref "J4") (pin "8") (pinfunction "8_8") (pintype "passive"))
      (node (ref "J41") (pin "8") (pinfunction "8_8") (pintype "passive"))
      (node (ref "J43") (pin "8") (pinfunction "8_8") (pintype "passive"))
      (node (ref "J47") (pin "8") (pinfunction "8_8") (pintype "passive"))
      (node (ref "J49") (pin "8") (pinfunction "8_8") (pintype "passive"))
      (node (ref "J8") (pin "8") (pinfunction "8_8") (pintype "passive"))
      (node (ref "R8") (pin "1") (pinfunction "1_1") (pintype "passive"))
    )
    (net (code "24") (name "/RE") (class "Default")
      (node (ref "J27") (pin "9") (pinfunction "9_9") (pintype "passive"))
      (node (ref "J54") (pin "5") (pinfunction "5_5") (pintype "passive"))
    )
    (net (code "25") (name "/RE0") (class "Default")
      (node (ref "1") (pin "16") (pinfunction "RE_16") (pintype "input"))
      (node (ref "J14") (pin "1") (pinfunction "1_1") (pintype "passive"))
      (node (ref "J2") (pin "9") (pinfunction "9_9") (pintype "passive"))
    )
    (net (code "26") (name "/RE1") (class "Default")
      (node (ref "3") (pin "16") (pinfunction "RE_16") (pintype "input"))
      (node (ref "J14") (pin "3") (pinfunction "3_3") (pintype "passive"))
      (node (ref "J8") (pin "9") (pinfunction "9_9") (pintype "passive"))
    )
    (net (code "27") (name "/RE2") (class "Default")
      (node (ref "5") (pin "16") (pinfunction "RE_16") (pintype "input"))
      (node (ref "J14") (pin "5") (pinfunction "5_5") (pintype "passive"))
      (node (ref "J16") (pin "9") (pinfunction "9_9") (pintype "passive"))
    )
    (net (code "28") (name "/RE3") (class "Default")
      (node (ref "7") (pin "16") (pinfunction "RE_16") (pintype "input"))
      (node (ref "J14") (pin "7") (pinfunction "7_7") (pintype "passive"))
      (node (ref "J22") (pin "9") (pinfunction "9_9") (pintype "passive"))
    )
    (net (code "29") (name "/RE4") (class "Default")
      (node (ref "9") (pin "16") (pinfunction "RE_16") (pintype "input"))
      (node (ref "J14") (pin "9") (pinfunction "9_9") (pintype "passive"))
      (node (ref "J29") (pin "9") (pinfunction "9_9") (pintype "passive"))
    )
    (net (code "30") (name "/RE5") (class "Default")
      (node (ref "11") (pin "16") (pinfunction "RE_16") (pintype "input"))
      (node (ref "J35") (pin "9") (pinfunction "9_9") (pintype "passive"))
      (node (ref "J52") (pin "1") (pinfunction "1_1") (pintype "passive"))
    )
    (net (code "31") (name "/RE6") (class "Default")
      (node (ref "13") (pin "16") (pinfunction "RE_16") (pintype "input"))
      (node (ref "J41") (pin "9") (pinfunction "9_9") (pintype "passive"))
      (node (ref "J52") (pin "3") (pinfunction "3_3") (pintype "passive"))
    )
    (net (code "32") (name "/RE7") (class "Default")
      (node (ref "15") (pin "16") (pinfunction "RE_16") (pintype "input"))
      (node (ref "J47") (pin "9") (pinfunction "9_9") (pintype "passive"))
      (node (ref "J52") (pin "5") (pinfunction "5_5") (pintype "passive"))
    )
    (net (code "33") (name "/RE8") (class "Default")
      (node (ref "16") (pin "16") (pinfunction "RE_16") (pintype "input"))
      (node (ref "J49") (pin "9") (pinfunction "9_9") (pintype "passive"))
      (node (ref "J52") (pin "7") (pinfunction "7_7") (pintype "passive"))
    )
    (net (code "34") (name "/RE9") (class "Default")
      (node (ref "14") (pin "16") (pinfunction "RE_16") (pintype "input"))
      (node (ref "J43") (pin "9") (pinfunction "9_9") (pintype "passive"))
      (node (ref "J52") (pin "9") (pinfunction "9_9") (pintype "passive"))
    )
    (net (code "35") (name "/RE10") (class "Default")
      (node (ref "12") (pin "16") (pinfunction "RE_16") (pintype "input"))
      (node (ref "J37") (pin "9") (pinfunction "9_9") (pintype "passive"))
      (node (ref "J53") (pin "1") (pinfunction "1_1") (pintype "passive"))
    )
    (net (code "36") (name "/RE11") (class "Default")
      (node (ref "10") (pin "16") (pinfunction "RE_16") (pintype "input"))
      (node (ref "J31") (pin "9") (pinfunction "9_9") (pintype "passive"))
      (node (ref "J53") (pin "3") (pinfunction "3_3") (pintype "passive"))
    )
    (net (code "37") (name "/RE12") (class "Default")
      (node (ref "8") (pin "16") (pinfunction "RE_16") (pintype "input"))
      (node (ref "J24") (pin "9") (pinfunction "9_9") (pintype "passive"))
      (node (ref "J53") (pin "5") (pinfunction "5_5") (pintype "passive"))
    )
    (net (code "38") (name "/RE13") (class "Default")
      (node (ref "6") (pin "16") (pinfunction "RE_16") (pintype "input"))
      (node (ref "J18") (pin "9") (pinfunction "9_9") (pintype "passive"))
      (node (ref "J53") (pin "7") (pinfunction "7_7") (pintype "passive"))
    )
    (net (code "39") (name "/RE14") (class "Default")
      (node (ref "4") (pin "16") (pinfunction "RE_16") (pintype "input"))
      (node (ref "J10") (pin "9") (pinfunction "9_9") (pintype "passive"))
      (node (ref "J53") (pin "9") (pinfunction "9_9") (pintype "passive"))
    )
    (net (code "40") (name "/RE15") (class "Default")
      (node (ref "2") (pin "16") (pinfunction "RE_16") (pintype "input"))
      (node (ref "J4") (pin "9") (pinfunction "9_9") (pintype "passive"))
      (node (ref "J54") (pin "7") (pinfunction "7_7") (pintype "passive"))
    )
    (net (code "41") (name "/WE") (class "Default")
      (node (ref "J27") (pin "10") (pinfunction "10_10") (pintype "passive"))
      (node (ref "J54") (pin "6") (pinfunction "6_6") (pintype "passive"))
    )
    (net (code "42") (name "/WE0") (class "Default")
      (node (ref "1") (pin "15") (pinfunction "WE_15") (pintype "input"))
      (node (ref "J14") (pin "2") (pinfunction "2_2") (pintype "passive"))
      (node (ref "J2") (pin "10") (pinfunction "10_10") (pintype "passive"))
    )
    (net (code "43") (name "/WE1") (class "Default")
      (node (ref "3") (pin "15") (pinfunction "WE_15") (pintype "input"))
      (node (ref "J14") (pin "4") (pinfunction "4_4") (pintype "passive"))
      (node (ref "J8") (pin "10") (pinfunction "10_10") (pintype "passive"))
    )
    (net (code "44") (name "/WE2") (class "Default")
      (node (ref "5") (pin "15") (pinfunction "WE_15") (pintype "input"))
      (node (ref "J14") (pin "6") (pinfunction "6_6") (pintype "passive"))
      (node (ref "J16") (pin "10") (pinfunction "10_10") (pintype "passive"))
    )
    (net (code "45") (name "/WE3") (class "Default")
      (node (ref "7") (pin "15") (pinfunction "WE_15") (pintype "input"))
      (node (ref "J14") (pin "8") (pinfunction "8_8") (pintype "passive"))
      (node (ref "J22") (pin "10") (pinfunction "10_10") (pintype "passive"))
    )
    (net (code "46") (name "/WE4") (class "Default")
      (node (ref "9") (pin "15") (pinfunction "WE_15") (pintype "input"))
      (node (ref "J14") (pin "10") (pinfunction "10_10") (pintype "passive"))
      (node (ref "J29") (pin "10") (pinfunction "10_10") (pintype "passive"))
    )
    (net (code "47") (name "/WE5") (class "Default")
      (node (ref "11") (pin "15") (pinfunction "WE_15") (pintype "input"))
      (node (ref "J35") (pin "10") (pinfunction "10_10") (pintype "passive"))
      (node (ref "J52") (pin "2") (pinfunction "2_2") (pintype "passive"))
    )
    (net (code "48") (name "/WE6") (class "Default")
      (node (ref "13") (pin "15") (pinfunction "WE_15") (pintype "input"))
      (node (ref "J41") (pin "10") (pinfunction "10_10") (pintype "passive"))
      (node (ref "J52") (pin "4") (pinfunction "4_4") (pintype "passive"))
    )
    (net (code "49") (name "/WE7") (class "Default")
      (node (ref "15") (pin "15") (pinfunction "WE_15") (pintype "input"))
      (node (ref "J47") (pin "10") (pinfunction "10_10") (pintype "passive"))
      (node (ref "J52") (pin "6") (pinfunction "6_6") (pintype "passive"))
    )
    (net (code "50") (name "/WE8") (class "Default")
      (node (ref "16") (pin "15") (pinfunction "WE_15") (pintype "input"))
      (node (ref "J49") (pin "10") (pinfunction "10_10") (pintype "passive"))
      (node (ref "J52") (pin "8") (pinfunction "8_8") (pintype "passive"))
    )
    (net (code "51") (name "/WE9") (class "Default")
      (node (ref "14") (pin "15") (pinfunction "WE_15") (pintype "input"))
      (node (ref "J43") (pin "10") (pinfunction "10_10") (pintype "passive"))
      (node (ref "J52") (pin "10") (pinfunction "10_10") (pintype "passive"))
    )
    (net (code "52") (name "/WE10") (class "Default")
      (node (ref "12") (pin "15") (pinfunction "WE_15") (pintype "input"))
      (node (ref "J37") (pin "10") (pinfunction "10_10") (pintype "passive"))
      (node (ref "J53") (pin "2") (pinfunction "2_2") (pintype "passive"))
    )
    (net (code "53") (name "/WE11") (class "Default")
      (node (ref "10") (pin "15") (pinfunction "WE_15") (pintype "input"))
      (node (ref "J31") (pin "10") (pinfunction "10_10") (pintype "passive"))
      (node (ref "J53") (pin "4") (pinfunction "4_4") (pintype "passive"))
    )
    (net (code "54") (name "/WE12") (class "Default")
      (node (ref "8") (pin "15") (pinfunction "WE_15") (pintype "input"))
      (node (ref "J24") (pin "10") (pinfunction "10_10") (pintype "passive"))
      (node (ref "J53") (pin "6") (pinfunction "6_6") (pintype "passive"))
    )
    (net (code "55") (name "/WE13") (class "Default")
      (node (ref "6") (pin "15") (pinfunction "WE_15") (pintype "input"))
      (node (ref "J18") (pin "10") (pinfunction "10_10") (pintype "passive"))
      (node (ref "J53") (pin "8") (pinfunction "8_8") (pintype "passive"))
    )
    (net (code "56") (name "/WE14") (class "Default")
      (node (ref "4") (pin "15") (pinfunction "WE_15") (pintype "input"))
      (node (ref "J10") (pin "10") (pinfunction "10_10") (pintype "passive"))
      (node (ref "J53") (pin "10") (pinfunction "10_10") (pintype "passive"))
    )
    (net (code "57") (name "/WE15") (class "Default")
      (node (ref "2") (pin "15") (pinfunction "WE_15") (pintype "input"))
      (node (ref "J4") (pin "10") (pinfunction "10_10") (pintype "passive"))
      (node (ref "J54") (pin "8") (pinfunction "8_8") (pintype "passive"))
    )
    (net (code "58") (name "GND") (class "Default")
      (node (ref "1") (pin "12") (pinfunction "GND_12") (pintype "power_in"))
      (node (ref "10") (pin "12") (pinfunction "GND_12") (pintype "power_in"))
      (node (ref "11") (pin "12") (pinfunction "GND_12") (pintype "power_in"))
      (node (ref "12") (pin "12") (pinfunction "GND_12") (pintype "power_in"))
      (node (ref "13") (pin "12") (pinfunction "GND_12") (pintype "power_in"))
      (node (ref "14") (pin "12") (pinfunction "GND_12") (pintype "power_in"))
      (node (ref "15") (pin "12") (pinfunction "GND_12") (pintype "power_in"))
      (node (ref "16") (pin "12") (pinfunction "GND_12") (pintype "power_in"))
      (node (ref "2") (pin "12") (pinfunction "GND_12") (pintype "power_in"))
      (node (ref "3") (pin "12") (pinfunction "GND_12") (pintype "power_in"))
      (node (ref "4") (pin "12") (pinfunction "GND_12") (pintype "power_in"))
      (node (ref "5") (pin "12") (pinfunction "GND_12") (pintype "power_in"))
      (node (ref "6") (pin "12") (pinfunction "GND_12") (pintype "power_in"))
      (node (ref "7") (pin "12") (pinfunction "GND_12") (pintype "power_in"))
      (node (ref "8") (pin "12") (pinfunction "GND_12") (pintype "power_in"))
      (node (ref "9") (pin "12") (pinfunction "GND_12") (pintype "power_in"))
      (node (ref "C1") (pin "1") (pinfunction "1_1") (pintype "passive"))
      (node (ref "C2") (pin "2") (pinfunction "2_2") (pintype "passive"))
      (node (ref "C3") (pin "2") (pinfunction "2_2") (pintype "passive"))
      (node (ref "C4") (pin "2") (pinfunction "2_2") (pintype "passive"))
      (node (ref "C5") (pin "2") (pinfunction "2_2") (pintype "passive"))
      (node (ref "D1") (pin "2") (pinfunction "K_2") (pintype "passive"))
      (node (ref "D2") (pin "2") (pinfunction "K_2") (pintype "passive"))
      (node (ref "D3") (pin "2") (pinfunction "K_2") (pintype "passive"))
      (node (ref "D4") (pin "2") (pinfunction "K_2") (pintype "passive"))
      (node (ref "D5") (pin "2") (pinfunction "K_2") (pintype "passive"))
      (node (ref "D6") (pin "2") (pinfunction "K_2") (pintype "passive"))
      (node (ref "D7") (pin "2") (pinfunction "K_2") (pintype "passive"))
      (node (ref "D8") (pin "2") (pinfunction "K_2") (pintype "passive"))
      (node (ref "J12") (pin "1") (pinfunction "1_1") (pintype "passive"))
      (node (ref "J13") (pin "1") (pinfunction "1_1") (pintype "passive"))
      (node (ref "J19") (pin "1") (pinfunction "1_1") (pintype "passive"))
      (node (ref "J20") (pin "1") (pinfunction "1_1") (pintype "passive"))
      (node (ref "J25") (pin "1") (pinfunction "1_1") (pintype "passive"))
      (node (ref "J26") (pin "1") (pinfunction "1_1") (pintype "passive"))
      (node (ref "J32") (pin "1") (pinfunction "1_1") (pintype "passive"))
      (node (ref "J33") (pin "1") (pinfunction "1_1") (pintype "passive"))
      (node (ref "J38") (pin "1") (pinfunction "1_1") (pintype "passive"))
      (node (ref "J39") (pin "1") (pinfunction "1_1") (pintype "passive"))
      (node (ref "J44") (pin "1") (pinfunction "1_1") (pintype "passive"))
      (node (ref "J45") (pin "1") (pinfunction "1_1") (pintype "passive"))
      (node (ref "J5") (pin "1") (pinfunction "1_1") (pintype "passive"))
      (node (ref "J50") (pin "1") (pinfunction "1_1") (pintype "passive"))
      (node (ref "J51") (pin "1") (pinfunction "1_1") (pintype "passive"))
      (node (ref "J54") (pin "10") (pinfunction "10_10") (pintype "passive"))
      (node (ref "J55") (pin "10") (pinfunction "10_10") (pintype "passive"))
      (node (ref "J6") (pin "1") (pinfunction "1_1") (pintype "passive"))
    )
    (net (code "59") (name "Net-(D1-A)") (class "Default")
      (node (ref "D1") (pin "1") (pinfunction "A_1") (pintype "passive"))
      (node (ref "R1") (pin "2") (pinfunction "2_2") (pintype "passive"))
    )
    (net (code "60") (name "Net-(D2-A)") (class "Default")
      (node (ref "D2") (pin "1") (pinfunction "A_1") (pintype "passive"))
      (node (ref "R2") (pin "2") (pinfunction "2_2") (pintype "passive"))
    )
    (net (code "61") (name "Net-(D3-A)") (class "Default")
      (node (ref "D3") (pin "1") (pinfunction "A_1") (pintype "passive"))
      (node (ref "R3") (pin "2") (pinfunction "2_2") (pintype "passive"))
    )
    (net (code "62") (name "Net-(D4-A)") (class "Default")
      (node (ref "D4") (pin "1") (pinfunction "A_1") (pintype "passive"))
      (node (ref "R4") (pin "2") (pinfunction "2_2") (pintype "passive"))
    )
    (net (code "63") (name "Net-(D5-A)") (class "Default")
      (node (ref "D5") (pin "1") (pinfunction "A_1") (pintype "passive"))
      (node (ref "R5") (pin "2") (pinfunction "2_2") (pintype "passive"))
    )
    (net (code "64") (name "Net-(D6-A)") (class "Default")
      (node (ref "D6") (pin "1") (pinfunction "A_1") (pintype "passive"))
      (node (ref "R6") (pin "2") (pinfunction "2_2") (pintype "passive"))
    )
    (net (code "65") (name "Net-(D7-A)") (class "Default")
      (node (ref "D7") (pin "1") (pinfunction "A_1") (pintype "passive"))
      (node (ref "R7") (pin "2") (pinfunction "2_2") (pintype "passive"))
    )
    (net (code "66") (name "Net-(D8-A)") (class "Default")
      (node (ref "D8") (pin "1") (pinfunction "A_1") (pintype "passive"))
      (node (ref "R8") (pin "2") (pinfunction "2_2") (pintype "passive"))
    )
    (net (code "67") (name "unconnected-(1-NC-Pad11)") (class "Default")
      (node (ref "1") (pin "11") (pinfunction "NC_11") (pintype "input+no_connect"))
    )
    (net (code "68") (name "unconnected-(1-NC-Pad14)") (class "Default")
      (node (ref "1") (pin "14") (pinfunction "NC_14") (pintype "input+no_connect"))
    )
    (net (code "69") (name "unconnected-(2-NC-Pad11)") (class "Default")
      (node (ref "2") (pin "11") (pinfunction "NC_11") (pintype "input+no_connect"))
    )
    (net (code "70") (name "unconnected-(2-NC-Pad14)") (class "Default")
      (node (ref "2") (pin "14") (pinfunction "NC_14") (pintype "input+no_connect"))
    )
    (net (code "71") (name "unconnected-(3-NC-Pad11)") (class "Default")
      (node (ref "3") (pin "11") (pinfunction "NC_11") (pintype "input+no_connect"))
    )
    (net (code "72") (name "unconnected-(3-NC-Pad14)") (class "Default")
      (node (ref "3") (pin "14") (pinfunction "NC_14") (pintype "input+no_connect"))
    )
    (net (code "73") (name "unconnected-(4-NC-Pad11)") (class "Default")
      (node (ref "4") (pin "11") (pinfunction "NC_11") (pintype "input+no_connect"))
    )
    (net (code "74") (name "unconnected-(4-NC-Pad14)") (class "Default")
      (node (ref "4") (pin "14") (pinfunction "NC_14") (pintype "input+no_connect"))
    )
    (net (code "75") (name "unconnected-(5-NC-Pad11)") (class "Default")
      (node (ref "5") (pin "11") (pinfunction "NC_11") (pintype "input+no_connect"))
    )
    (net (code "76") (name "unconnected-(5-NC-Pad14)") (class "Default")
      (node (ref "5") (pin "14") (pinfunction "NC_14") (pintype "input+no_connect"))
    )
    (net (code "77") (name "unconnected-(6-NC-Pad11)") (class "Default")
      (node (ref "6") (pin "11") (pinfunction "NC_11") (pintype "input+no_connect"))
    )
    (net (code "78") (name "unconnected-(6-NC-Pad14)") (class "Default")
      (node (ref "6") (pin "14") (pinfunction "NC_14") (pintype "input+no_connect"))
    )
    (net (code "79") (name "unconnected-(7-NC-Pad11)") (class "Default")
      (node (ref "7") (pin "11") (pinfunction "NC_11") (pintype "input+no_connect"))
    )
    (net (code "80") (name "unconnected-(7-NC-Pad14)") (class "Default")
      (node (ref "7") (pin "14") (pinfunction "NC_14") (pintype "input+no_connect"))
    )
    (net (code "81") (name "unconnected-(8-NC-Pad11)") (class "Default")
      (node (ref "8") (pin "11") (pinfunction "NC_11") (pintype "input+no_connect"))
    )
    (net (code "82") (name "unconnected-(8-NC-Pad14)") (class "Default")
      (node (ref "8") (pin "14") (pinfunction "NC_14") (pintype "input+no_connect"))
    )
    (net (code "83") (name "unconnected-(9-NC-Pad11)") (class "Default")
      (node (ref "9") (pin "11") (pinfunction "NC_11") (pintype "input+no_connect"))
    )
    (net (code "84") (name "unconnected-(9-NC-Pad14)") (class "Default")
      (node (ref "9") (pin "14") (pinfunction "NC_14") (pintype "input+no_connect"))
    )
    (net (code "85") (name "unconnected-(10-NC-Pad11)") (class "Default")
      (node (ref "10") (pin "11") (pinfunction "NC_11") (pintype "input+no_connect"))
    )
    (net (code "86") (name "unconnected-(10-NC-Pad14)") (class "Default")
      (node (ref "10") (pin "14") (pinfunction "NC_14") (pintype "input+no_connect"))
    )
    (net (code "87") (name "unconnected-(11-NC-Pad11)") (class "Default")
      (node (ref "11") (pin "11") (pinfunction "NC_11") (pintype "input+no_connect"))
    )
    (net (code "88") (name "unconnected-(11-NC-Pad14)") (class "Default")
      (node (ref "11") (pin "14") (pinfunction "NC_14") (pintype "input+no_connect"))
    )
    (net (code "89") (name "unconnected-(12-NC-Pad11)") (class "Default")
      (node (ref "12") (pin "11") (pinfunction "NC_11") (pintype "input+no_connect"))
    )
    (net (code "90") (name "unconnected-(12-NC-Pad14)") (class "Default")
      (node (ref "12") (pin "14") (pinfunction "NC_14") (pintype "input+no_connect"))
    )
    (net (code "91") (name "unconnected-(13-NC-Pad11)") (class "Default")
      (node (ref "13") (pin "11") (pinfunction "NC_11") (pintype "input+no_connect"))
    )
    (net (code "92") (name "unconnected-(13-NC-Pad14)") (class "Default")
      (node (ref "13") (pin "14") (pinfunction "NC_14") (pintype "input+no_connect"))
    )
    (net (code "93") (name "unconnected-(14-NC-Pad11)") (class "Default")
      (node (ref "14") (pin "11") (pinfunction "NC_11") (pintype "input+no_connect"))
    )
    (net (code "94") (name "unconnected-(14-NC-Pad14)") (class "Default")
      (node (ref "14") (pin "14") (pinfunction "NC_14") (pintype "input+no_connect"))
    )
    (net (code "95") (name "unconnected-(15-NC-Pad11)") (class "Default")
      (node (ref "15") (pin "11") (pinfunction "NC_11") (pintype "input+no_connect"))
    )
    (net (code "96") (name "unconnected-(15-NC-Pad14)") (class "Default")
      (node (ref "15") (pin "14") (pinfunction "NC_14") (pintype "input+no_connect"))
    )
    (net (code "97") (name "unconnected-(16-NC-Pad11)") (class "Default")
      (node (ref "16") (pin "11") (pinfunction "NC_11") (pintype "input+no_connect"))
    )
    (net (code "98") (name "unconnected-(16-NC-Pad14)") (class "Default")
      (node (ref "16") (pin "14") (pinfunction "NC_14") (pintype "input+no_connect"))
    )
    (net (code "99") (name "unconnected-(J5-Pad2)") (class "Default")
      (node (ref "J5") (pin "2") (pinfunction "2_2") (pintype "passive+no_connect"))
    )
    (net (code "100") (name "unconnected-(J5-Pad3)") (class "Default")
      (node (ref "J5") (pin "3") (pinfunction "3_3") (pintype "passive+no_connect"))
    )
    (net (code "101") (name "unconnected-(J6-Pad2)") (class "Default")
      (node (ref "J6") (pin "2") (pinfunction "2_2") (pintype "passive+no_connect"))
    )
    (net (code "102") (name "unconnected-(J6-Pad3)") (class "Default")
      (node (ref "J6") (pin "3") (pinfunction "3_3") (pintype "passive+no_connect"))
    )
    (net (code "103") (name "unconnected-(J12-Pad2)") (class "Default")
      (node (ref "J12") (pin "2") (pinfunction "2_2") (pintype "passive+no_connect"))
    )
    (net (code "104") (name "unconnected-(J12-Pad3)") (class "Default")
      (node (ref "J12") (pin "3") (pinfunction "3_3") (pintype "passive+no_connect"))
    )
    (net (code "105") (name "unconnected-(J13-Pad2)") (class "Default")
      (node (ref "J13") (pin "2") (pinfunction "2_2") (pintype "passive+no_connect"))
    )
    (net (code "106") (name "unconnected-(J13-Pad3)") (class "Default")
      (node (ref "J13") (pin "3") (pinfunction "3_3") (pintype "passive+no_connect"))
    )
    (net (code "107") (name "unconnected-(J19-Pad2)") (class "Default")
      (node (ref "J19") (pin "2") (pinfunction "2_2") (pintype "passive+no_connect"))
    )
    (net (code "108") (name "unconnected-(J19-Pad3)") (class "Default")
      (node (ref "J19") (pin "3") (pinfunction "3_3") (pintype "passive+no_connect"))
    )
    (net (code "109") (name "unconnected-(J20-Pad2)") (class "Default")
      (node (ref "J20") (pin "2") (pinfunction "2_2") (pintype "passive+no_connect"))
    )
    (net (code "110") (name "unconnected-(J20-Pad3)") (class "Default")
      (node (ref "J20") (pin "3") (pinfunction "3_3") (pintype "passive+no_connect"))
    )
    (net (code "111") (name "unconnected-(J25-Pad2)") (class "Default")
      (node (ref "J25") (pin "2") (pinfunction "2_2") (pintype "passive+no_connect"))
    )
    (net (code "112") (name "unconnected-(J25-Pad3)") (class "Default")
      (node (ref "J25") (pin "3") (pinfunction "3_3") (pintype "passive+no_connect"))
    )
    (net (code "113") (name "unconnected-(J26-Pad2)") (class "Default")
      (node (ref "J26") (pin "2") (pinfunction "2_2") (pintype "passive+no_connect"))
    )
    (net (code "114") (name "unconnected-(J26-Pad3)") (class "Default")
      (node (ref "J26") (pin "3") (pinfunction "3_3") (pintype "passive+no_connect"))
    )
    (net (code "115") (name "unconnected-(J32-Pad2)") (class "Default")
      (node (ref "J32") (pin "2") (pinfunction "2_2") (pintype "passive+no_connect"))
    )
    (net (code "116") (name "unconnected-(J32-Pad3)") (class "Default")
      (node (ref "J32") (pin "3") (pinfunction "3_3") (pintype "passive+no_connect"))
    )
    (net (code "117") (name "unconnected-(J33-Pad2)") (class "Default")
      (node (ref "J33") (pin "2") (pinfunction "2_2") (pintype "passive+no_connect"))
    )
    (net (code "118") (name "unconnected-(J33-Pad3)") (class "Default")
      (node (ref "J33") (pin "3") (pinfunction "3_3") (pintype "passive+no_connect"))
    )
    (net (code "119") (name "unconnected-(J38-Pad2)") (class "Default")
      (node (ref "J38") (pin "2") (pinfunction "2_2") (pintype "passive+no_connect"))
    )
    (net (code "120") (name "unconnected-(J38-Pad3)") (class "Default")
      (node (ref "J38") (pin "3") (pinfunction "3_3") (pintype "passive+no_connect"))
    )
    (net (code "121") (name "unconnected-(J39-Pad2)") (class "Default")
      (node (ref "J39") (pin "2") (pinfunction "2_2") (pintype "passive+no_connect"))
    )
    (net (code "122") (name "unconnected-(J39-Pad3)") (class "Default")
      (node (ref "J39") (pin "3") (pinfunction "3_3") (pintype "passive+no_connect"))
    )
    (net (code "123") (name "unconnected-(J44-Pad2)") (class "Default")
      (node (ref "J44") (pin "2") (pinfunction "2_2") (pintype "passive+no_connect"))
    )
    (net (code "124") (name "unconnected-(J44-Pad3)") (class "Default")
      (node (ref "J44") (pin "3") (pinfunction "3_3") (pintype "passive+no_connect"))
    )
    (net (code "125") (name "unconnected-(J45-Pad2)") (class "Default")
      (node (ref "J45") (pin "2") (pinfunction "2_2") (pintype "passive+no_connect"))
    )
    (net (code "126") (name "unconnected-(J45-Pad3)") (class "Default")
      (node (ref "J45") (pin "3") (pinfunction "3_3") (pintype "passive+no_connect"))
    )
    (net (code "127") (name "unconnected-(J50-Pad2)") (class "Default")
      (node (ref "J50") (pin "2") (pinfunction "2_2") (pintype "passive+no_connect"))
    )
    (net (code "128") (name "unconnected-(J50-Pad3)") (class "Default")
      (node (ref "J50") (pin "3") (pinfunction "3_3") (pintype "passive+no_connect"))
    )
    (net (code "129") (name "unconnected-(J51-Pad2)") (class "Default")
      (node (ref "J51") (pin "2") (pinfunction "2_2") (pintype "passive+no_connect"))
    )
    (net (code "130") (name "unconnected-(J51-Pad3)") (class "Default")
      (node (ref "J51") (pin "3") (pinfunction "3_3") (pintype "passive+no_connect"))
    )
    (net (code "131") (name "unconnected-(J55-Pad5)") (class "Default")
      (node (ref "J55") (pin "5") (pinfunction "5_5") (pintype "passive"))
    )
    (net (code "132") (name "unconnected-(J55-Pad6)") (class "Default")
      (node (ref "J55") (pin "6") (pinfunction "6_6") (pintype "passive"))
    )
    (net (code "133") (name "unconnected-(J55-Pad7)") (class "Default")
      (node (ref "J55") (pin "7") (pinfunction "7_7") (pintype "passive"))
    )
    (net (code "134") (name "unconnected-(J55-Pad8)") (class "Default")
      (node (ref "J55") (pin "8") (pinfunction "8_8") (pintype "passive"))
    )
  )
)
